# module.net
KiCad netlist of a schematic drawn in EAGLE
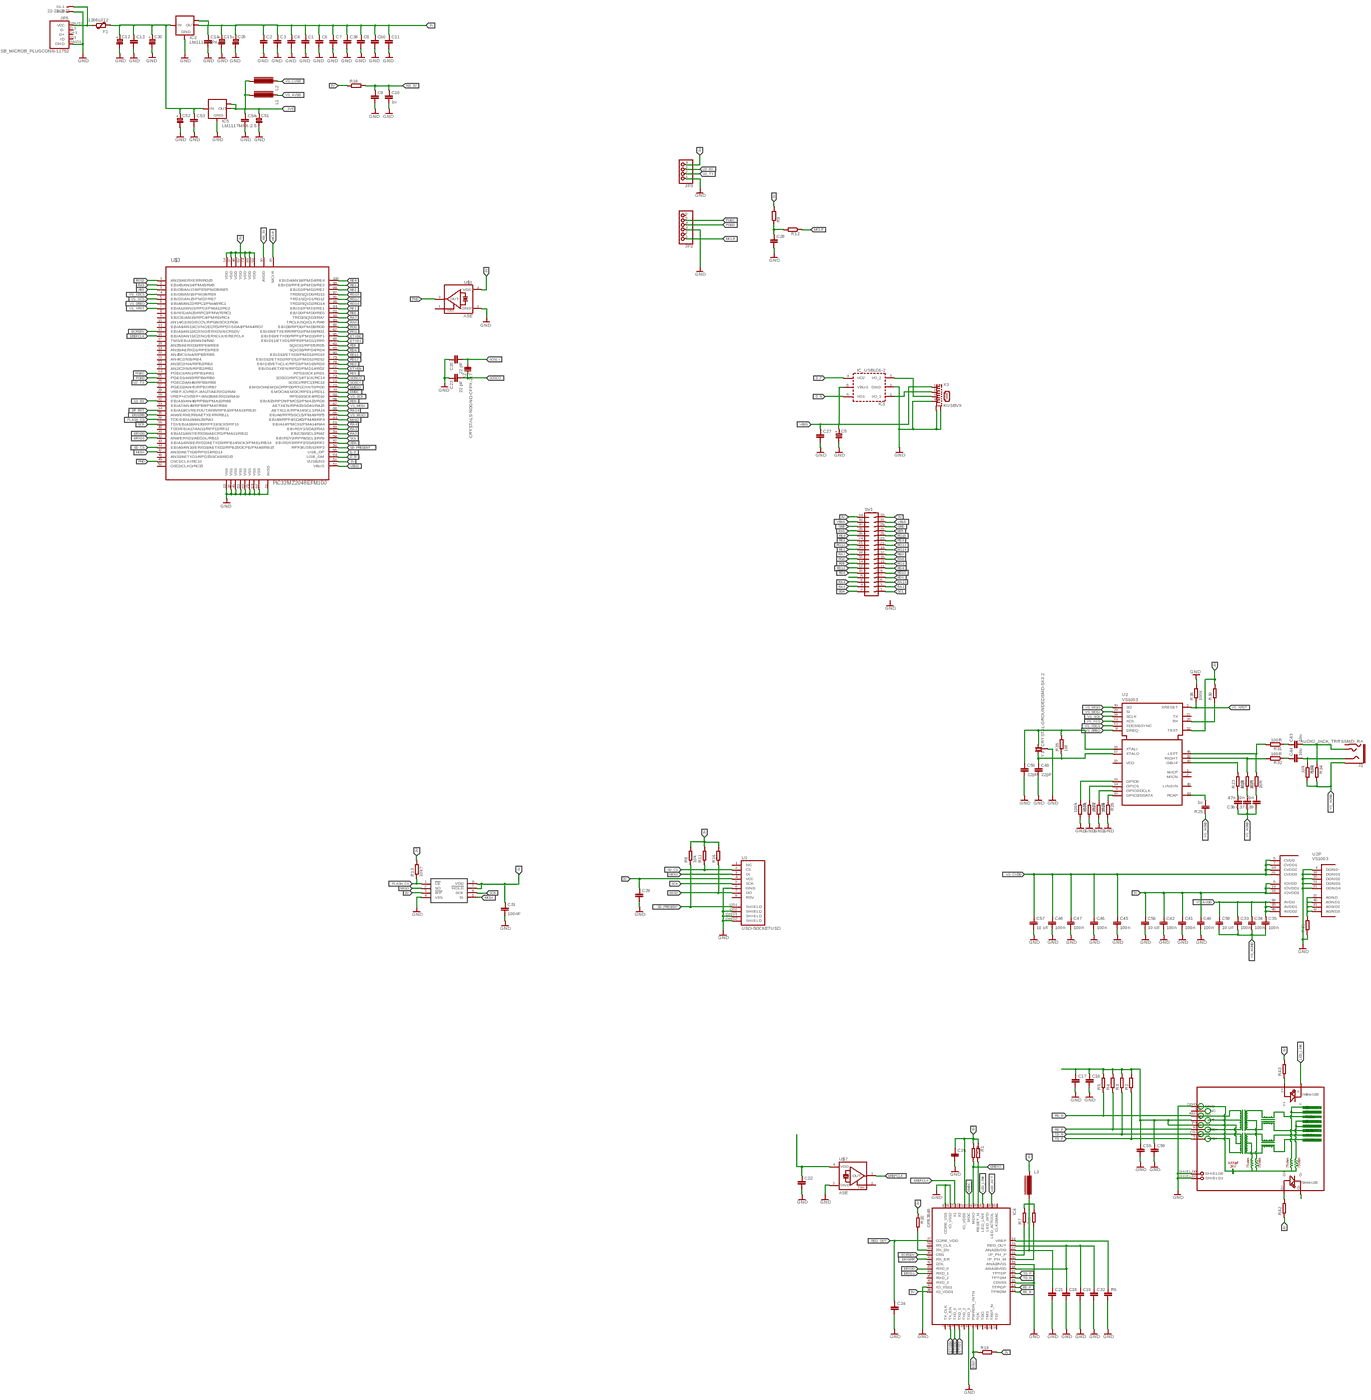
[diagram p0: schematic, sheet 1, overview]
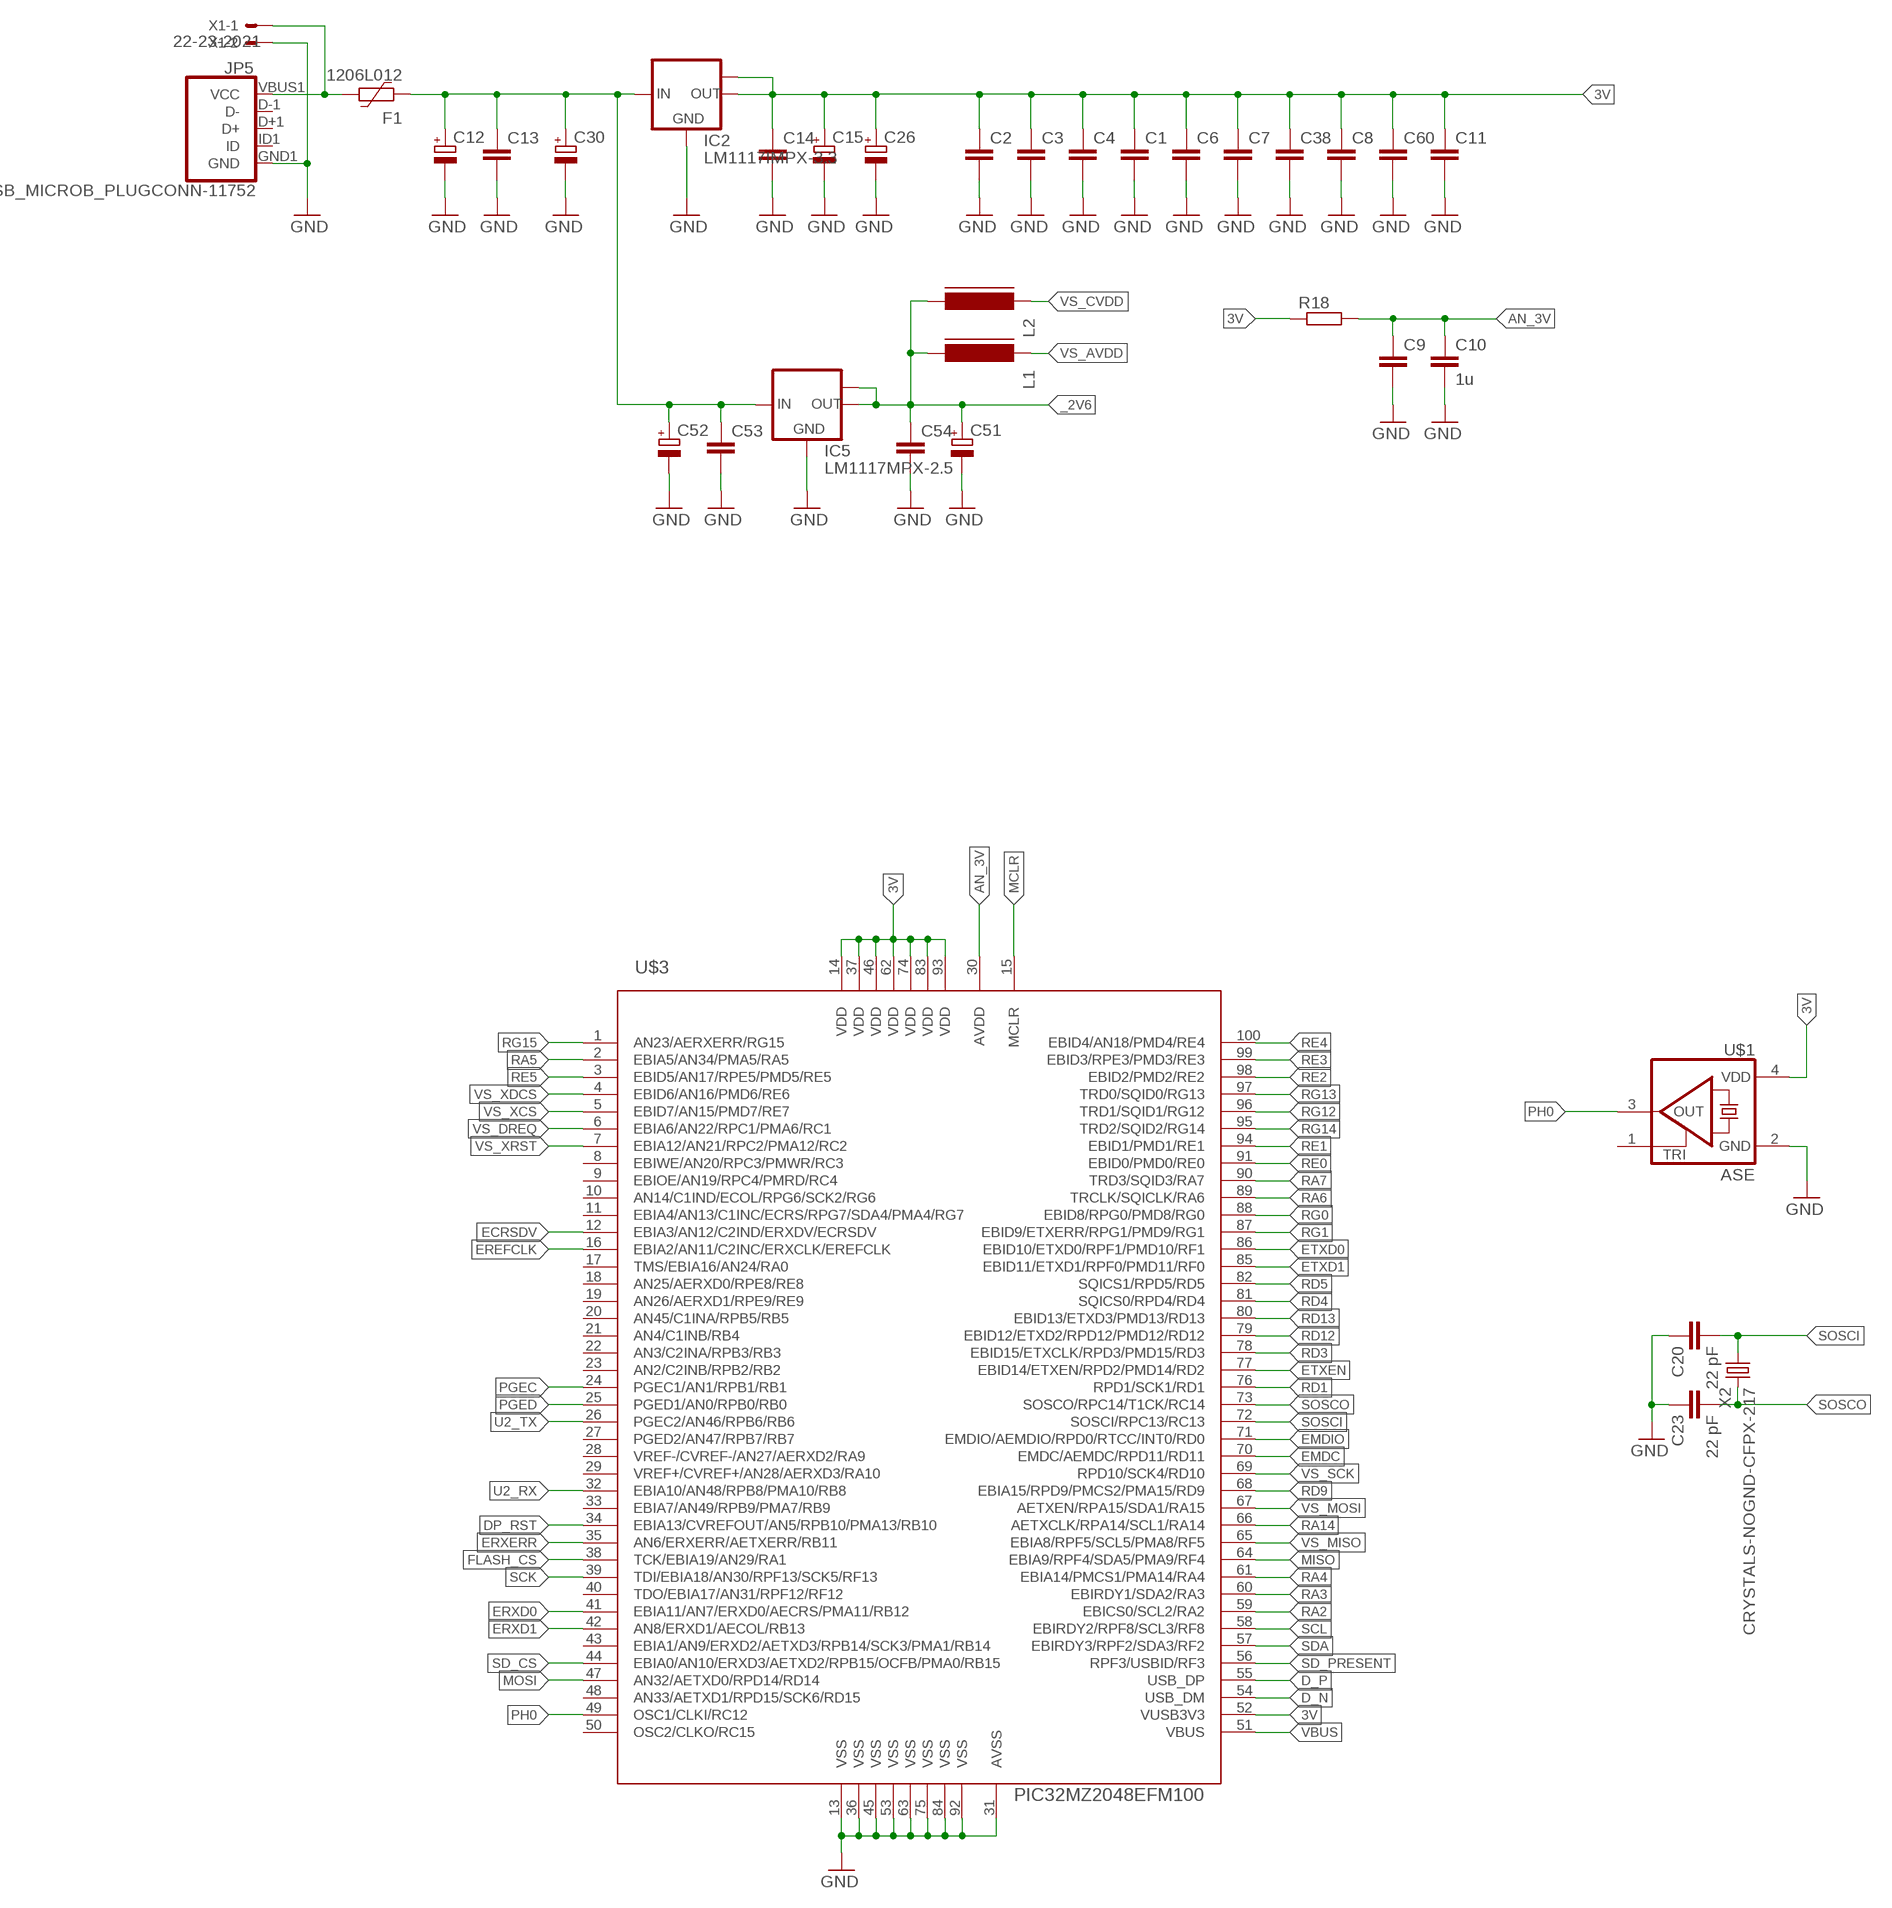
[diagram p1: schematic, sheet 1, part 1 of 4]
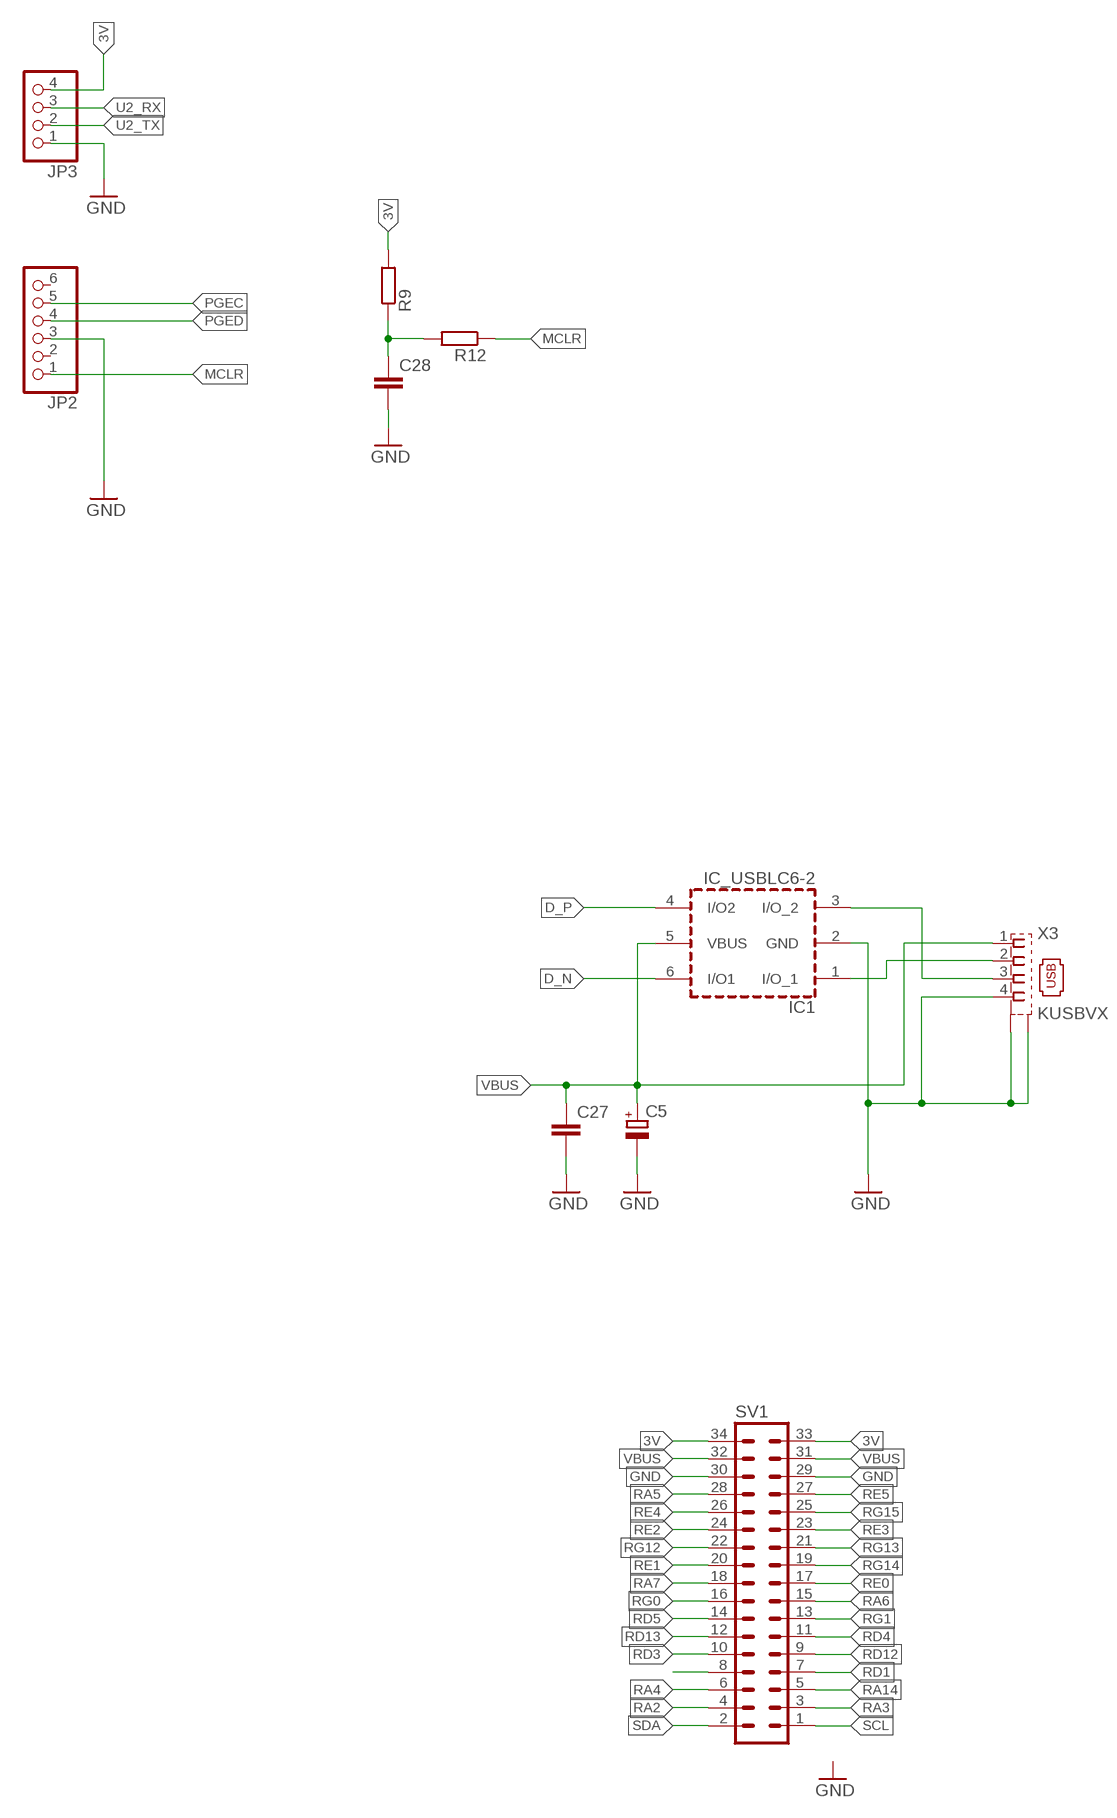
[diagram p2: schematic, sheet 1, part 2 of 4]
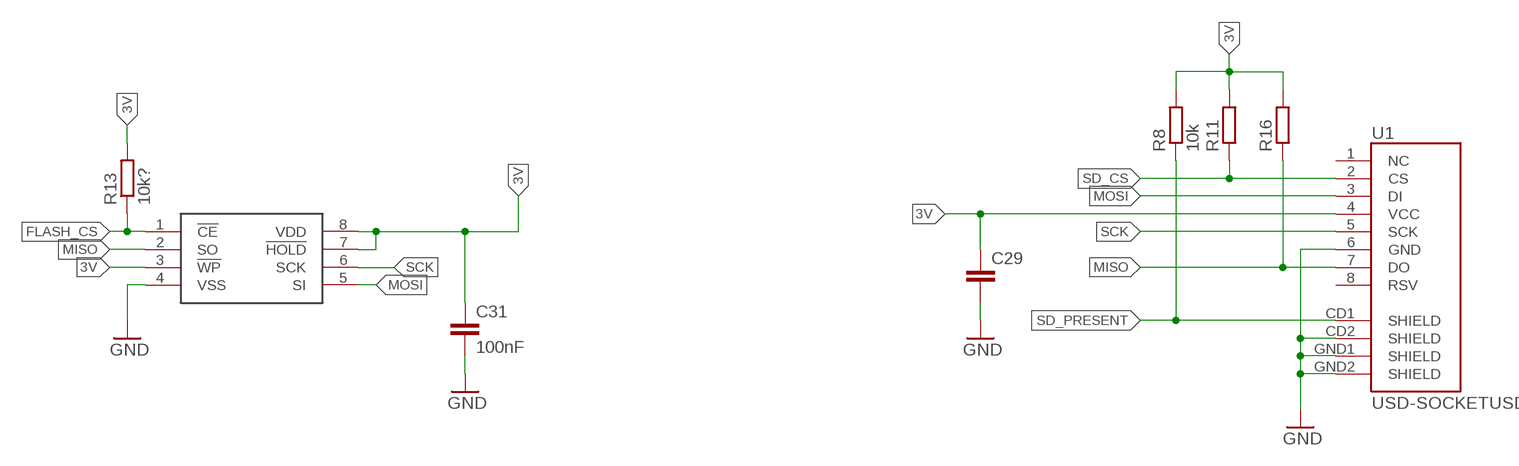
[diagram p3: schematic, sheet 1, part 3 of 4]
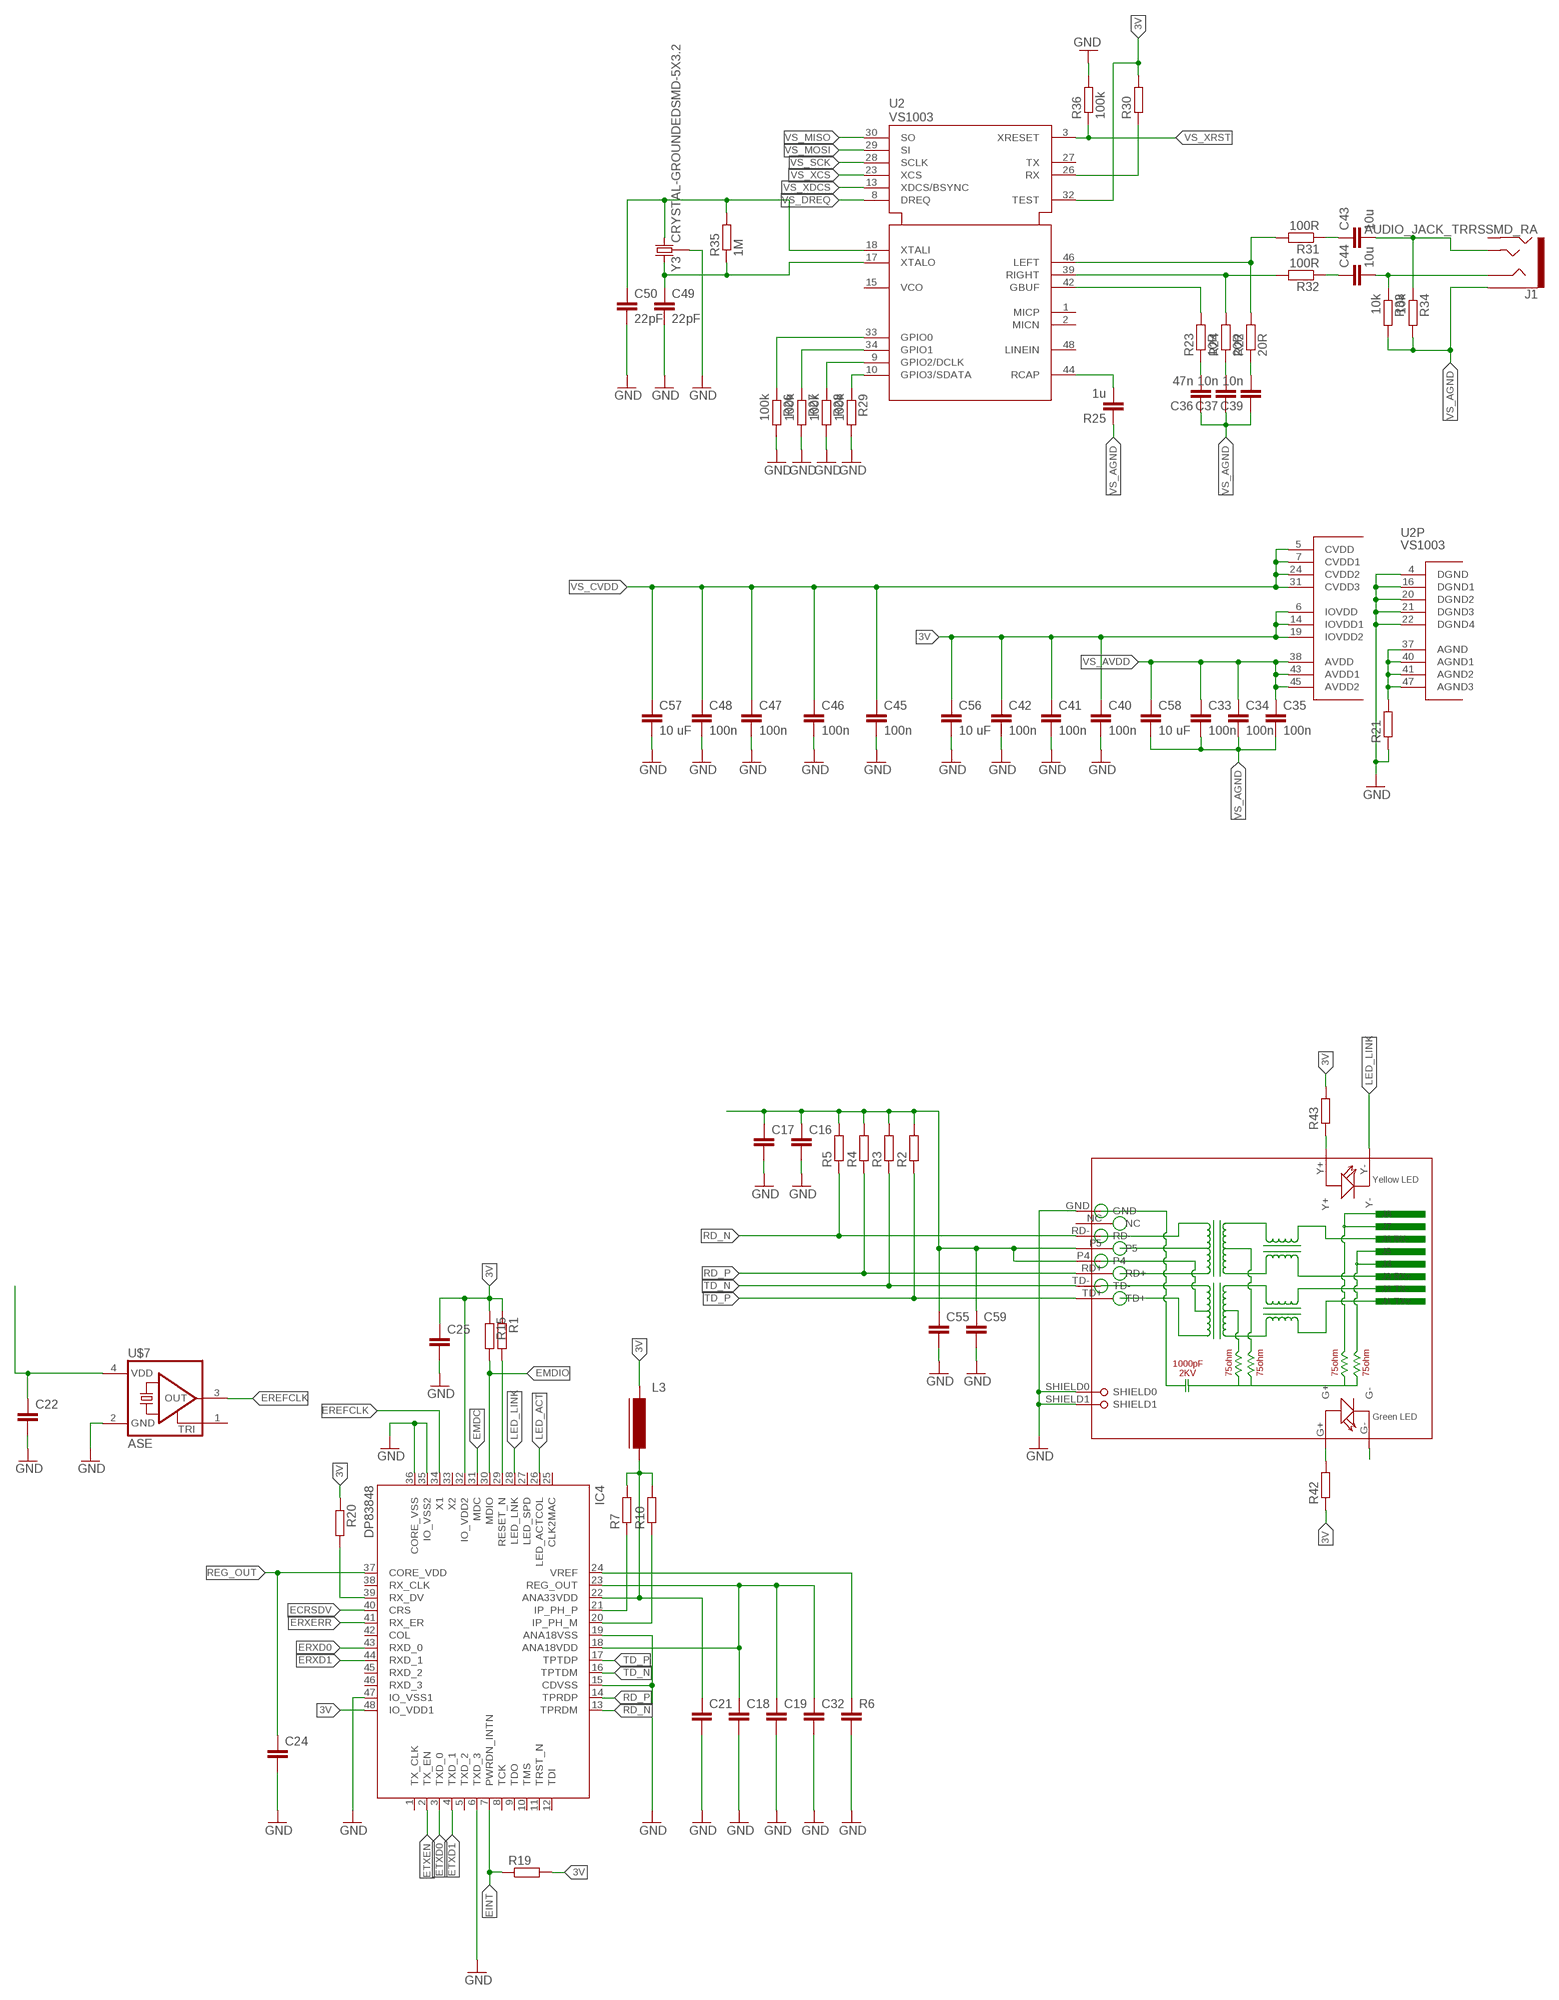
[diagram p4: schematic, sheet 1, part 4 of 4]

(export (version "E")
  (design (tool "Eeschema 10.0.6"))
  (components
    (comp (ref "C1")
      (value "C-EUC0402")
      (footprint "eagle-import:C0402")
      (libsource (lib "eagle-import") (part "C-EUC0402"))
    )
    (comp (ref "C2")
      (value "C-EUC0402")
      (footprint "eagle-import:C0402")
      (libsource (lib "eagle-import") (part "C-EUC0402"))
    )
    (comp (ref "C3")
      (value "C-EUC0402")
      (footprint "eagle-import:C0402")
      (libsource (lib "eagle-import") (part "C-EUC0402"))
    )
    (comp (ref "C4")
      (value "C-EUC0402")
      (footprint "eagle-import:C0402")
      (libsource (lib "eagle-import") (part "C-EUC0402"))
    )
    (comp (ref "C5")
      (value "CPOL-EUSMCA")
      (footprint "eagle-import:SMC_A")
      (libsource (lib "eagle-import") (part "CPOL-EUSMCA"))
    )
    (comp (ref "C6")
      (value "C-EUC0402")
      (footprint "eagle-import:C0402")
      (libsource (lib "eagle-import") (part "C-EUC0402"))
    )
    (comp (ref "C7")
      (value "C-EUC0402")
      (footprint "eagle-import:C0402")
      (libsource (lib "eagle-import") (part "C-EUC0402"))
    )
    (comp (ref "C8")
      (value "C-EUC0402")
      (footprint "eagle-import:C0402")
      (libsource (lib "eagle-import") (part "C-EUC0402"))
    )
    (comp (ref "C9")
      (value "C-EUC0402")
      (footprint "eagle-import:C0402")
      (libsource (lib "eagle-import") (part "C-EUC0402"))
    )
    (comp (ref "C10")
      (value "1u")
      (footprint "eagle-import:C0603")
      (libsource (lib "eagle-import") (part "C-EUC0603"))
    )
    (comp (ref "C11")
      (value "C-EUC0402")
      (footprint "eagle-import:C0402")
      (libsource (lib "eagle-import") (part "C-EUC0402"))
    )
    (comp (ref "C12")
      (value "CPOL-EUSMCB")
      (footprint "eagle-import:SMC_B")
      (libsource (lib "eagle-import") (part "CPOL-EUSMCB"))
    )
    (comp (ref "C13")
      (value "C-EUC0603")
      (footprint "eagle-import:C0603")
      (libsource (lib "eagle-import") (part "C-EUC0603"))
    )
    (comp (ref "C14")
      (value "C-EUC0603")
      (footprint "eagle-import:C0603")
      (libsource (lib "eagle-import") (part "C-EUC0603"))
    )
    (comp (ref "C15")
      (value "CPOL-EUSMCB")
      (footprint "eagle-import:SMC_B")
      (libsource (lib "eagle-import") (part "CPOL-EUSMCB"))
    )
    (comp (ref "C16")
      (value "C-EUC0603")
      (footprint "eagle-import:C0603")
      (libsource (lib "eagle-import") (part "C-EUC0603"))
    )
    (comp (ref "C17")
      (value "C-EUC0603")
      (footprint "eagle-import:C0603")
      (libsource (lib "eagle-import") (part "C-EUC0603"))
    )
    (comp (ref "C18")
      (value "C-EUC0402")
      (footprint "eagle-import:C0402")
      (libsource (lib "eagle-import") (part "C-EUC0402"))
    )
    (comp (ref "C19")
      (value "C-EUC0402")
      (footprint "eagle-import:C0402")
      (libsource (lib "eagle-import") (part "C-EUC0402"))
    )
    (comp (ref "C20")
      (value "22 pF")
      (footprint "eagle-import:C0603")
      (libsource (lib "eagle-import") (part "C-EUC0603"))
    )
    (comp (ref "C21")
      (value "C-EUC0402")
      (footprint "eagle-import:C0402")
      (libsource (lib "eagle-import") (part "C-EUC0402"))
    )
    (comp (ref "C22")
      (value "C-EUC0402")
      (footprint "eagle-import:C0402")
      (libsource (lib "eagle-import") (part "C-EUC0402"))
    )
    (comp (ref "C23")
      (value "22 pF")
      (footprint "eagle-import:C0603")
      (libsource (lib "eagle-import") (part "C-EUC0603"))
    )
    (comp (ref "C24")
      (value "C-EUC0603")
      (footprint "eagle-import:C0603")
      (libsource (lib "eagle-import") (part "C-EUC0603"))
    )
    (comp (ref "C25")
      (value "C-EUC0603")
      (footprint "eagle-import:C0603")
      (libsource (lib "eagle-import") (part "C-EUC0603"))
    )
    (comp (ref "C26")
      (value "CPOL-EUSMCA")
      (footprint "eagle-import:SMC_A")
      (libsource (lib "eagle-import") (part "CPOL-EUSMCA"))
    )
    (comp (ref "C27")
      (value "C-EUC0603")
      (footprint "eagle-import:C0603")
      (libsource (lib "eagle-import") (part "C-EUC0603"))
    )
    (comp (ref "C28")
      (value "C-EUC0603")
      (footprint "eagle-import:C0603")
      (libsource (lib "eagle-import") (part "C-EUC0603"))
    )
    (comp (ref "C29")
      (value "C-EUC0603")
      (footprint "eagle-import:C0603")
      (libsource (lib "eagle-import") (part "C-EUC0603"))
    )
    (comp (ref "C30")
      (value "CPOL-EUSMCA")
      (footprint "eagle-import:SMC_A")
      (libsource (lib "eagle-import") (part "CPOL-EUSMCA"))
    )
    (comp (ref "C31")
      (value "100nF")
      (footprint "eagle-import:C0603")
      (libsource (lib "eagle-import") (part "C-EUC0603"))
    )
    (comp (ref "C32")
      (value "C-EUC0603")
      (footprint "eagle-import:C0603")
      (libsource (lib "eagle-import") (part "C-EUC0603"))
    )
    (comp (ref "C33")
      (value "100n")
      (footprint "eagle-import:C0603")
      (libsource (lib "eagle-import") (part "C-EUC0603"))
    )
    (comp (ref "C34")
      (value "100n")
      (footprint "eagle-import:C0603")
      (libsource (lib "eagle-import") (part "C-EUC0603"))
    )
    (comp (ref "C35")
      (value "100n")
      (footprint "eagle-import:C0603")
      (libsource (lib "eagle-import") (part "C-EUC0603"))
    )
    (comp (ref "C36")
      (value "47n")
      (footprint "eagle-import:C0603")
      (libsource (lib "eagle-import") (part "C-EUC0603"))
    )
    (comp (ref "C37")
      (value "10n")
      (footprint "eagle-import:C0603")
      (libsource (lib "eagle-import") (part "C-EUC0603"))
    )
    (comp (ref "C38")
      (value "C-EUC0402")
      (footprint "eagle-import:C0402")
      (libsource (lib "eagle-import") (part "C-EUC0402"))
    )
    (comp (ref "C39")
      (value "10n")
      (footprint "eagle-import:C0603")
      (libsource (lib "eagle-import") (part "C-EUC0603"))
    )
    (comp (ref "C40")
      (value "100n")
      (footprint "eagle-import:C0402")
      (libsource (lib "eagle-import") (part "C-EUC0402"))
    )
    (comp (ref "C41")
      (value "100n")
      (footprint "eagle-import:C0402")
      (libsource (lib "eagle-import") (part "C-EUC0402"))
    )
    (comp (ref "C42")
      (value "100n")
      (footprint "eagle-import:C0402")
      (libsource (lib "eagle-import") (part "C-EUC0402"))
    )
    (comp (ref "C43")
      (value "10u")
      (footprint "eagle-import:C0603")
      (libsource (lib "eagle-import") (part "C-EUC0603"))
    )
    (comp (ref "C44")
      (value "10u")
      (footprint "eagle-import:C0603")
      (libsource (lib "eagle-import") (part "C-EUC0603"))
    )
    (comp (ref "C45")
      (value "100n")
      (footprint "eagle-import:C0402")
      (libsource (lib "eagle-import") (part "C-EUC0402"))
    )
    (comp (ref "C46")
      (value "100n")
      (footprint "eagle-import:C0603")
      (libsource (lib "eagle-import") (part "C-EUC0603"))
    )
    (comp (ref "C47")
      (value "100n")
      (footprint "eagle-import:C0603")
      (libsource (lib "eagle-import") (part "C-EUC0603"))
    )
    (comp (ref "C48")
      (value "100n")
      (footprint "eagle-import:C0603")
      (libsource (lib "eagle-import") (part "C-EUC0603"))
    )
    (comp (ref "C49")
      (value "22pF")
      (footprint "eagle-import:C0603")
      (libsource (lib "eagle-import") (part "C-EUC0603"))
    )
    (comp (ref "C50")
      (value "22pF")
      (footprint "eagle-import:C0603")
      (libsource (lib "eagle-import") (part "C-EUC0603"))
    )
    (comp (ref "C51")
      (value "CPOL-EUSMCB")
      (footprint "eagle-import:SMC_B")
      (libsource (lib "eagle-import") (part "CPOL-EUSMCB"))
    )
    (comp (ref "C52")
      (value "CPOL-EUSMCB")
      (footprint "eagle-import:SMC_B")
      (libsource (lib "eagle-import") (part "CPOL-EUSMCB"))
    )
    (comp (ref "C53")
      (value "C-EUC1206")
      (footprint "eagle-import:C1206")
      (libsource (lib "eagle-import") (part "C-EUC1206"))
    )
    (comp (ref "C54")
      (value "C-EUC1206")
      (footprint "eagle-import:C1206")
      (libsource (lib "eagle-import") (part "C-EUC1206"))
    )
    (comp (ref "C55")
      (value "C-EUC0603")
      (footprint "eagle-import:C0603")
      (libsource (lib "eagle-import") (part "C-EUC0603"))
    )
    (comp (ref "C56")
      (value "10 uF")
      (footprint "eagle-import:C0603")
      (libsource (lib "eagle-import") (part "C-EUC0603"))
    )
    (comp (ref "C57")
      (value "10 uF")
      (footprint "eagle-import:C0603")
      (libsource (lib "eagle-import") (part "C-EUC0603"))
    )
    (comp (ref "C58")
      (value "10 uF")
      (footprint "eagle-import:C0603")
      (libsource (lib "eagle-import") (part "C-EUC0603"))
    )
    (comp (ref "C59")
      (value "C-EUC0603")
      (footprint "eagle-import:C0603")
      (libsource (lib "eagle-import") (part "C-EUC0603"))
    )
    (comp (ref "C60")
      (value "C-EUC0402")
      (footprint "eagle-import:C0402")
      (libsource (lib "eagle-import") (part "C-EUC0402"))
    )
    (comp (ref "F1")
      (value "1206L012")
      (footprint "eagle-import:1206L")
      (fields (field (name "MF") "Littelfuse"))
      (libsource (lib "eagle-import") (part "?1206L012"))
    )
    (comp (ref "IC1")
      (value "IC_USBLC6-2")
      (footprint "eagle-import:SOT-23-6L")
      (libsource (lib "eagle-import") (part "IC_USBLC6-2"))
    )
    (comp (ref "IC2")
      (value "LM1117IMPX-3.3")
      (footprint "eagle-import:SOT223")
      (libsource (lib "eagle-import") (part "LM1117IMPX-3.3"))
    )
    (comp (ref "IC4")
      (value "DP83848")
      (footprint "eagle-import:LQFP48")
      (fields (field (name "MPN") "DP83848VYB"))
      (libsource (lib "eagle-import") (part "DP83848"))
    )
    (comp (ref "IC5")
      (value "LM1117MPX-2.5")
      (footprint "eagle-import:SOT223")
      (libsource (lib "eagle-import") (part "LM1117MPX-2.5"))
    )
    (comp (ref "J1")
      (value "AUDIO_JACK_TRRSSMD_RA")
      (footprint "eagle-import:AUDIO_JACK_3.5MM_TRRS_SMD_RA")
      (libsource (lib "eagle-import") (part "AUDIO_JACK_TRRSSMD_RA"))
    )
    (comp (ref "JP2")
      (value "PINHD-1X6")
      (footprint "eagle-import:1X06")
      (libsource (lib "eagle-import") (part "PINHD-1X6"))
    )
    (comp (ref "JP3")
      (value "PINHD-1X4")
      (footprint "eagle-import:1X04")
      (libsource (lib "eagle-import") (part "PINHD-1X4"))
    )
    (comp (ref "JP5")
      (value "USB_MICROB_PLUGCONN-11752")
      (footprint "eagle-import:USB-B-MICRO-SMD_V03")
      (libsource (lib "eagle-import") (part "USB_MICROB_PLUGCONN-11752"))
    )
    (comp (ref "L1")
      (value "FERRITE-0805")
      (footprint "eagle-import:FB805")
      (libsource (lib "eagle-import") (part "FERRITE-0805"))
    )
    (comp (ref "L2")
      (value "FERRITE-0805")
      (footprint "eagle-import:FB805")
      (libsource (lib "eagle-import") (part "FERRITE-0805"))
    )
    (comp (ref "L3")
      (value "FERRITE-0805")
      (footprint "eagle-import:FB805")
      (libsource (lib "eagle-import") (part "FERRITE-0805"))
    )
    (comp (ref "R1")
      (value "R-EU_R0402")
      (footprint "eagle-import:R0402")
      (libsource (lib "eagle-import") (part "R-EU_R0402"))
    )
    (comp (ref "R2")
      (value "R-EU_R0603")
      (footprint "eagle-import:R0603")
      (libsource (lib "eagle-import") (part "R-EU_R0603"))
    )
    (comp (ref "R3")
      (value "R-EU_R0603")
      (footprint "eagle-import:R0603")
      (libsource (lib "eagle-import") (part "R-EU_R0603"))
    )
    (comp (ref "R4")
      (value "R-EU_R0603")
      (footprint "eagle-import:R0603")
      (libsource (lib "eagle-import") (part "R-EU_R0603"))
    )
    (comp (ref "R5")
      (value "R-EU_R0603")
      (footprint "eagle-import:R0603")
      (libsource (lib "eagle-import") (part "R-EU_R0603"))
    )
    (comp (ref "R6")
      (value "C-EUC0603")
      (footprint "eagle-import:C0603")
      (libsource (lib "eagle-import") (part "C-EUC0603"))
    )
    (comp (ref "R7")
      (value "R-EU_R0402")
      (footprint "eagle-import:R0402")
      (libsource (lib "eagle-import") (part "R-EU_R0402"))
    )
    (comp (ref "R8")
      (value "10k")
      (footprint "eagle-import:R0603")
      (libsource (lib "eagle-import") (part "R-EU_R0603"))
    )
    (comp (ref "R9")
      (value "R-EU_R0603")
      (footprint "eagle-import:R0603")
      (libsource (lib "eagle-import") (part "R-EU_R0603"))
    )
    (comp (ref "R10")
      (value "R-EU_R0402")
      (footprint "eagle-import:R0402")
      (libsource (lib "eagle-import") (part "R-EU_R0402"))
    )
    (comp (ref "R11")
      (value "R-EU_R0603")
      (footprint "eagle-import:R0603")
      (libsource (lib "eagle-import") (part "R-EU_R0603"))
    )
    (comp (ref "R12")
      (value "R-EU_R0402")
      (footprint "eagle-import:R0402")
      (libsource (lib "eagle-import") (part "R-EU_R0402"))
    )
    (comp (ref "R13")
      (value "10k?")
      (footprint "eagle-import:R0603")
      (libsource (lib "eagle-import") (part "R-EU_R0603"))
    )
    (comp (ref "R15")
      (value "R-EU_R0603")
      (footprint "eagle-import:R0603")
      (libsource (lib "eagle-import") (part "R-EU_R0603"))
    )
    (comp (ref "R16")
      (value "R-EU_R0603")
      (footprint "eagle-import:R0603")
      (libsource (lib "eagle-import") (part "R-EU_R0603"))
    )
    (comp (ref "R18")
      (value "R-EU_R0805")
      (footprint "eagle-import:R0805")
      (libsource (lib "eagle-import") (part "R-EU_R0805"))
    )
    (comp (ref "R19")
      (value "R-EU_R0402")
      (footprint "eagle-import:R0402")
      (libsource (lib "eagle-import") (part "R-EU_R0402"))
    )
    (comp (ref "R20")
      (value "R-EU_R0603")
      (footprint "eagle-import:R0603")
      (libsource (lib "eagle-import") (part "R-EU_R0603"))
    )
    (comp (ref "R21")
      (value "R-EU_R0603")
      (footprint "eagle-import:R0603")
      (libsource (lib "eagle-import") (part "R-EU_R0603"))
    )
    (comp (ref "R22")
      (value "20R")
      (footprint "eagle-import:R0603")
      (libsource (lib "eagle-import") (part "R-EU_R0603"))
    )
    (comp (ref "R23")
      (value "10R")
      (footprint "eagle-import:R0603")
      (libsource (lib "eagle-import") (part "R-EU_R0603"))
    )
    (comp (ref "R24")
      (value "20R")
      (footprint "eagle-import:R0603")
      (libsource (lib "eagle-import") (part "R-EU_R0603"))
    )
    (comp (ref "R25")
      (value "1u")
      (footprint "eagle-import:C0603")
      (libsource (lib "eagle-import") (part "C-EUC0603"))
    )
    (comp (ref "R26")
      (value "100k")
      (footprint "eagle-import:R0402")
      (libsource (lib "eagle-import") (part "R-EU_R0402"))
    )
    (comp (ref "R27")
      (value "100k")
      (footprint "eagle-import:R0402")
      (libsource (lib "eagle-import") (part "R-EU_R0402"))
    )
    (comp (ref "R28")
      (value "100k")
      (footprint "eagle-import:R0402")
      (libsource (lib "eagle-import") (part "R-EU_R0402"))
    )
    (comp (ref "R29")
      (value "100k")
      (footprint "eagle-import:R0402")
      (libsource (lib "eagle-import") (part "R-EU_R0402"))
    )
    (comp (ref "R30")
      (value "R-EU_0204/7")
      (footprint "eagle-import:0204_7")
      (libsource (lib "eagle-import") (part "R-EU_0204/7"))
    )
    (comp (ref "R31")
      (value "100R")
      (footprint "eagle-import:R0603")
      (libsource (lib "eagle-import") (part "R-EU_R0603"))
    )
    (comp (ref "R32")
      (value "100R")
      (footprint "eagle-import:R0603")
      (libsource (lib "eagle-import") (part "R-EU_R0603"))
    )
    (comp (ref "R33")
      (value "10k")
      (footprint "eagle-import:R0603")
      (libsource (lib "eagle-import") (part "R-EU_R0603"))
    )
    (comp (ref "R34")
      (value "10k")
      (footprint "eagle-import:R0603")
      (libsource (lib "eagle-import") (part "R-EU_R0603"))
    )
    (comp (ref "R35")
      (value "1M")
      (footprint "eagle-import:R0603")
      (libsource (lib "eagle-import") (part "R-EU_R0603"))
    )
    (comp (ref "R36")
      (value "100k")
      (footprint "eagle-import:R0603")
      (libsource (lib "eagle-import") (part "R-EU_R0603"))
    )
    (comp (ref "R42")
      (value "R-EU_R0603")
      (footprint "eagle-import:R0603")
      (libsource (lib "eagle-import") (part "R-EU_R0603"))
    )
    (comp (ref "R43")
      (value "R-EU_R0603")
      (footprint "eagle-import:R0603")
      (libsource (lib "eagle-import") (part "R-EU_R0603"))
    )
    (comp (ref "RJ1")
      (value "HR911105A")
      (footprint "eagle-import:HR911105A")
      (libsource (lib "eagle-import") (part "HR911105A"))
    )
    (comp (ref "SV1")
      (value "ML34L")
      (footprint "eagle-import:ML34L")
      (libsource (lib "eagle-import") (part "ML34L"))
    )
    (comp (ref "U$1")
      (value "ASE")
      (footprint "eagle-import:ASE")
      (libsource (lib "eagle-import") (part "ASE"))
    )
    (comp (ref "U$2")
      (value "SST25VF016BSO8M")
      (footprint "eagle-import:SO-08M")
      (libsource (lib "eagle-import") (part "SST25VF016BSO8M"))
    )
    (comp (ref "U$3")
      (value "PIC32MZ2048EFM100")
      (footprint "eagle-import:TQFP100_12X12")
      (libsource (lib "eagle-import") (part "PIC32MZ2048EFM100"))
    )
    (comp (ref "U$7")
      (value "ASE")
      (footprint "eagle-import:ASE")
      (libsource (lib "eagle-import") (part "ASE"))
    )
    (comp (ref "U1")
      (value "USD-SOCKETUSD")
      (footprint "eagle-import:USD-SOCKET-PP")
      (libsource (lib "eagle-import") (part "USD-SOCKETUSD"))
    )
    (comp (ref "U2")
      (value "VS1003")
      (footprint "eagle-import:LQFP48")
      (libsource (lib "eagle-import") (part "VS1003"))
    )
    (comp (ref "X1")
      (value "22-23-2021")
      (footprint "eagle-import:22-23-2021")
      (fields (field (name "MF") "MOLEX"))
      (libsource (lib "eagle-import") (part "22-23-2021"))
    )
    (comp (ref "X2")
      (value "CRYSTALS-NOGND-CFPX-217")
      (footprint "eagle-import:3.2X1.5-2-PAD")
      (libsource (lib "eagle-import") (part "CRYSTALS-NOGND-CFPX-217"))
    )
    (comp (ref "X3")
      (value "KUSBVX")
      (footprint "eagle-import:KUSBVX")
      (libsource (lib "eagle-import") (part "KUSBVX"))
    )
    (comp (ref "Y3")
      (value "CRYSTAL-GROUNDEDSMD-5X3.2")
      (footprint "eagle-import:CRYSTAL-SMD-5X3.2-4PAD")
      (libsource (lib "eagle-import") (part "CRYSTAL-GROUNDEDSMD-5X3.2"))
    )
  )
  (nets
    (net (code "1") (name "/A3V") (class "Default")
      (node (ref "C16") (pin "1") (pinfunction "1_1") (pintype "passive"))
      (node (ref "C17") (pin "1") (pinfunction "1_1") (pintype "passive"))
      (node (ref "C21") (pin "1") (pinfunction "1_1") (pintype "passive"))
      (node (ref "C55") (pin "1") (pinfunction "1_1") (pintype "passive"))
      (node (ref "C59") (pin "1") (pinfunction "1_1") (pintype "passive"))
      (node (ref "IC4") (pin "22") (pinfunction "ANA33VDD_22") (pintype "power_in"))
      (node (ref "L3") (pin "2") (pinfunction "2_2") (pintype "passive"))
      (node (ref "R10") (pin "2") (pinfunction "2_2") (pintype "passive"))
      (node (ref "R2") (pin "2") (pinfunction "2_2") (pintype "passive"))
      (node (ref "R3") (pin "2") (pinfunction "2_2") (pintype "passive"))
      (node (ref "R4") (pin "2") (pinfunction "2_2") (pintype "passive"))
      (node (ref "R5") (pin "2") (pinfunction "2_2") (pintype "passive"))
      (node (ref "R7") (pin "2") (pinfunction "2_2") (pintype "passive"))
      (node (ref "RJ1") (pin "P4") (pinfunction "P4_P4") (pintype "bidirectional"))
      (node (ref "RJ1") (pin "P5") (pinfunction "P5_P5") (pintype "bidirectional"))
    )
    (net (code "2") (name "3V") (class "Default")
      (node (ref "C1") (pin "1") (pinfunction "1_1") (pintype "passive"))
      (node (ref "C11") (pin "1") (pinfunction "1_1") (pintype "passive"))
      (node (ref "C14") (pin "1") (pinfunction "1_1") (pintype "passive"))
      (node (ref "C15") (pin "+") (pinfunction "+_+") (pintype "passive"))
      (node (ref "C2") (pin "1") (pinfunction "1_1") (pintype "passive"))
      (node (ref "C22") (pin "1") (pinfunction "1_1") (pintype "passive"))
      (node (ref "C25") (pin "1") (pinfunction "1_1") (pintype "passive"))
      (node (ref "C26") (pin "+") (pinfunction "+_+") (pintype "passive"))
      (node (ref "C29") (pin "1") (pinfunction "1_1") (pintype "passive"))
      (node (ref "C3") (pin "1") (pinfunction "1_1") (pintype "passive"))
      (node (ref "C31") (pin "1") (pinfunction "1_1") (pintype "passive"))
      (node (ref "C38") (pin "1") (pinfunction "1_1") (pintype "passive"))
      (node (ref "C4") (pin "1") (pinfunction "1_1") (pintype "passive"))
      (node (ref "C40") (pin "1") (pinfunction "1_1") (pintype "passive"))
      (node (ref "C41") (pin "1") (pinfunction "1_1") (pintype "passive"))
      (node (ref "C42") (pin "1") (pinfunction "1_1") (pintype "passive"))
      (node (ref "C56") (pin "1") (pinfunction "1_1") (pintype "passive"))
      (node (ref "C6") (pin "1") (pinfunction "1_1") (pintype "passive"))
      (node (ref "C60") (pin "1") (pinfunction "1_1") (pintype "passive"))
      (node (ref "C7") (pin "1") (pinfunction "1_1") (pintype "passive"))
      (node (ref "C8") (pin "1") (pinfunction "1_1") (pintype "passive"))
      (node (ref "IC2") (pin "2") (pinfunction "OUT_2") (pintype "passive"))
      (node (ref "IC2") (pin "TAB") (pinfunction "OUT1_TAB") (pintype "passive"))
      (node (ref "IC4") (pin "32") (pinfunction "IO_VDD2_32") (pintype "power_in"))
      (node (ref "IC4") (pin "48") (pinfunction "IO_VDD1_48") (pintype "power_in"))
      (node (ref "JP3") (pin "4") (pinfunction "4_4") (pintype "passive"))
      (node (ref "L3") (pin "1") (pinfunction "1_1") (pintype "passive"))
      (node (ref "R1") (pin "1") (pinfunction "1_1") (pintype "passive"))
      (node (ref "R11") (pin "2") (pinfunction "2_2") (pintype "passive"))
      (node (ref "R13") (pin "2") (pinfunction "2_2") (pintype "passive"))
      (node (ref "R15") (pin "1") (pinfunction "1_1") (pintype "passive"))
      (node (ref "R16") (pin "2") (pinfunction "2_2") (pintype "passive"))
      (node (ref "R18") (pin "1") (pinfunction "1_1") (pintype "passive"))
      (node (ref "R19") (pin "2") (pinfunction "2_2") (pintype "passive"))
      (node (ref "R20") (pin "1") (pinfunction "1_1") (pintype "passive"))
      (node (ref "R30") (pin "2") (pinfunction "2_2") (pintype "passive"))
      (node (ref "R42") (pin "1") (pinfunction "1_1") (pintype "passive"))
      (node (ref "R43") (pin "2") (pinfunction "2_2") (pintype "passive"))
      (node (ref "R8") (pin "2") (pinfunction "2_2") (pintype "passive"))
      (node (ref "R9") (pin "2") (pinfunction "2_2") (pintype "passive"))
      (node (ref "SV1") (pin "33") (pinfunction "33_33") (pintype "passive"))
      (node (ref "SV1") (pin "34") (pinfunction "34_34") (pintype "passive"))
      (node (ref "U$1") (pin "4") (pinfunction "VDD_4") (pintype "power_in"))
      (node (ref "U$2") (pin "3") (pinfunction "~{WP}_3") (pintype "bidirectional"))
      (node (ref "U$2") (pin "7") (pinfunction "~{HOLD}_7") (pintype "bidirectional"))
      (node (ref "U$2") (pin "8") (pinfunction "VDD_8") (pintype "bidirectional"))
      (node (ref "U$3") (pin "14") (pinfunction "VDD_14") (pintype "bidirectional"))
      (node (ref "U$3") (pin "37") (pinfunction "VDD_37") (pintype "bidirectional"))
      (node (ref "U$3") (pin "46") (pinfunction "VDD_46") (pintype "bidirectional"))
      (node (ref "U$3") (pin "52") (pinfunction "VUSB3V3_52") (pintype "bidirectional"))
      (node (ref "U$3") (pin "62") (pinfunction "VDD_62") (pintype "bidirectional"))
      (node (ref "U$3") (pin "74") (pinfunction "VDD_74") (pintype "bidirectional"))
      (node (ref "U$3") (pin "83") (pinfunction "VDD_83") (pintype "bidirectional"))
      (node (ref "U$3") (pin "93") (pinfunction "VDD_93") (pintype "bidirectional"))
      (node (ref "U$7") (pin "4") (pinfunction "VDD_4") (pintype "power_in"))
      (node (ref "U1") (pin "4") (pinfunction "VCC_4") (pintype "bidirectional"))
      (node (ref "U2") (pin "14") (pinfunction "IOVDD1_14") (pintype "power_in"))
      (node (ref "U2") (pin "19") (pinfunction "IOVDD2_19") (pintype "power_in"))
      (node (ref "U2") (pin "32") (pinfunction "TEST_32") (pintype "bidirectional"))
      (node (ref "U2") (pin "6") (pinfunction "IOVDD_6") (pintype "power_in"))
    )
    (net (code "3") (name "AN_3V") (class "Default")
      (node (ref "C10") (pin "1") (pinfunction "1_1") (pintype "passive"))
      (node (ref "C9") (pin "1") (pinfunction "1_1") (pintype "passive"))
      (node (ref "R18") (pin "2") (pinfunction "2_2") (pintype "passive"))
      (node (ref "U$3") (pin "30") (pinfunction "AVDD_30") (pintype "bidirectional"))
    )
    (net (code "4") (name "DP_RST") (class "Default")
      (node (ref "IC4") (pin "29") (pinfunction "RESET_N_29") (pintype "input"))
      (node (ref "R1") (pin "2") (pinfunction "2_2") (pintype "passive"))
      (node (ref "U$3") (pin "34") (pinfunction "EBIA13/CVREFOUT/AN5/RPB10/PMA13/RB10_34") (pintype "bidirectional"))
    )
    (net (code "5") (name "D_N") (class "Default")
      (node (ref "IC1") (pin "6") (pinfunction "I/O1_6") (pintype "bidirectional"))
      (node (ref "U$3") (pin "54") (pinfunction "USB_DM_54") (pintype "bidirectional"))
    )
    (net (code "6") (name "D_P") (class "Default")
      (node (ref "IC1") (pin "4") (pinfunction "I/O2_4") (pintype "bidirectional"))
      (node (ref "U$3") (pin "55") (pinfunction "USB_DP_55") (pintype "bidirectional"))
    )
    (net (code "7") (name "ECRSDV") (class "Default")
      (node (ref "IC4") (pin "40") (pinfunction "CRS_40") (pintype "bidirectional"))
      (node (ref "U$3") (pin "12") (pinfunction "EBIA3/AN12/C2IND/ERXDV/ECRSDV_12") (pintype "bidirectional"))
    )
    (net (code "8") (name "EINT") (class "Default")
      (node (ref "IC4") (pin "7") (pinfunction "PWRDN_INTN_7") (pintype "bidirectional"))
      (node (ref "R19") (pin "1") (pinfunction "1_1") (pintype "passive"))
    )
    (net (code "9") (name "EMDC") (class "Default")
      (node (ref "IC4") (pin "31") (pinfunction "MDC_31") (pintype "input"))
      (node (ref "U$3") (pin "70") (pinfunction "EMDC/AEMDC/RPD11/RD11_70") (pintype "bidirectional"))
    )
    (net (code "10") (name "EMDIO") (class "Default")
      (node (ref "IC4") (pin "30") (pinfunction "MDIO_30") (pintype "bidirectional"))
      (node (ref "R15") (pin "2") (pinfunction "2_2") (pintype "passive"))
      (node (ref "U$3") (pin "71") (pinfunction "EMDIO/AEMDIO/RPD0/RTCC/INT0/RD0_71") (pintype "bidirectional"))
    )
    (net (code "11") (name "EREFCLK") (class "Default")
      (node (ref "IC4") (pin "34") (pinfunction "X1_34") (pintype "input"))
      (node (ref "U$3") (pin "16") (pinfunction "EBIA2/AN11/C2INC/ERXCLK/EREFCLK_16") (pintype "bidirectional"))
      (node (ref "U$7") (pin "3") (pinfunction "OUT_3") (pintype "output"))
    )
    (net (code "12") (name "ERXD0") (class "Default")
      (node (ref "IC4") (pin "43") (pinfunction "RXD_0_43") (pintype "bidirectional"))
      (node (ref "U$3") (pin "41") (pinfunction "EBIA11/AN7/ERXD0/AECRS/PMA11/RB12_41") (pintype "bidirectional"))
    )
    (net (code "13") (name "ERXD1") (class "Default")
      (node (ref "IC4") (pin "44") (pinfunction "RXD_1_44") (pintype "bidirectional"))
      (node (ref "U$3") (pin "42") (pinfunction "AN8/ERXD1/AECOL/RB13_42") (pintype "bidirectional"))
    )
    (net (code "14") (name "ERXERR") (class "Default")
      (node (ref "IC4") (pin "41") (pinfunction "RX_ER_41") (pintype "bidirectional"))
      (node (ref "U$3") (pin "35") (pinfunction "AN6/ERXERR/AETXERR/RB11_35") (pintype "bidirectional"))
    )
    (net (code "15") (name "ETXD0") (class "Default")
      (node (ref "IC4") (pin "3") (pinfunction "TXD_0_3") (pintype "bidirectional"))
      (node (ref "U$3") (pin "86") (pinfunction "EBID10/ETXD0/RPF1/PMD10/RF1_86") (pintype "bidirectional"))
    )
    (net (code "16") (name "ETXD1") (class "Default")
      (node (ref "IC4") (pin "4") (pinfunction "TXD_1_4") (pintype "bidirectional"))
      (node (ref "U$3") (pin "85") (pinfunction "EBID11/ETXD1/RPF0/PMD11/RF0_85") (pintype "bidirectional"))
    )
    (net (code "17") (name "ETXEN") (class "Default")
      (node (ref "IC4") (pin "2") (pinfunction "TX_EN_2") (pintype "bidirectional"))
      (node (ref "U$3") (pin "77") (pinfunction "EBID14/ETXEN/RPD2/PMD14/RD2_77") (pintype "bidirectional"))
    )
    (net (code "18") (name "FLASH_CS") (class "Default")
      (node (ref "R13") (pin "1") (pinfunction "1_1") (pintype "passive"))
      (node (ref "U$2") (pin "1") (pinfunction "~{CE}_1") (pintype "bidirectional"))
      (node (ref "U$3") (pin "38") (pinfunction "TCK/EBIA19/AN29/RA1_38") (pintype "bidirectional"))
    )
    (net (code "19") (name "GND") (class "Default")
      (node (ref "C1") (pin "2") (pinfunction "2_2") (pintype "passive"))
      (node (ref "C10") (pin "2") (pinfunction "2_2") (pintype "passive"))
      (node (ref "C11") (pin "2") (pinfunction "2_2") (pintype "passive"))
      (node (ref "C12") (pin "-") (pinfunction "-_-") (pintype "passive"))
      (node (ref "C13") (pin "2") (pinfunction "2_2") (pintype "passive"))
      (node (ref "C14") (pin "2") (pinfunction "2_2") (pintype "passive"))
      (node (ref "C15") (pin "-") (pinfunction "-_-") (pintype "passive"))
      (node (ref "C16") (pin "2") (pinfunction "2_2") (pintype "passive"))
      (node (ref "C17") (pin "2") (pinfunction "2_2") (pintype "passive"))
      (node (ref "C18") (pin "2") (pinfunction "2_2") (pintype "passive"))
      (node (ref "C19") (pin "2") (pinfunction "2_2") (pintype "passive"))
      (node (ref "C2") (pin "2") (pinfunction "2_2") (pintype "passive"))
      (node (ref "C20") (pin "1") (pinfunction "1_1") (pintype "passive"))
      (node (ref "C21") (pin "2") (pinfunction "2_2") (pintype "passive"))
      (node (ref "C22") (pin "2") (pinfunction "2_2") (pintype "passive"))
      (node (ref "C23") (pin "1") (pinfunction "1_1") (pintype "passive"))
      (node (ref "C24") (pin "2") (pinfunction "2_2") (pintype "passive"))
      (node (ref "C25") (pin "2") (pinfunction "2_2") (pintype "passive"))
      (node (ref "C26") (pin "-") (pinfunction "-_-") (pintype "passive"))
      (node (ref "C27") (pin "2") (pinfunction "2_2") (pintype "passive"))
      (node (ref "C28") (pin "2") (pinfunction "2_2") (pintype "passive"))
      (node (ref "C29") (pin "2") (pinfunction "2_2") (pintype "passive"))
      (node (ref "C3") (pin "2") (pinfunction "2_2") (pintype "passive"))
      (node (ref "C30") (pin "-") (pinfunction "-_-") (pintype "passive"))
      (node (ref "C31") (pin "2") (pinfunction "2_2") (pintype "passive"))
      (node (ref "C32") (pin "2") (pinfunction "2_2") (pintype "passive"))
      (node (ref "C38") (pin "2") (pinfunction "2_2") (pintype "passive"))
      (node (ref "C4") (pin "2") (pinfunction "2_2") (pintype "passive"))
      (node (ref "C40") (pin "2") (pinfunction "2_2") (pintype "passive"))
      (node (ref "C41") (pin "2") (pinfunction "2_2") (pintype "passive"))
      (node (ref "C42") (pin "2") (pinfunction "2_2") (pintype "passive"))
      (node (ref "C45") (pin "2") (pinfunction "2_2") (pintype "passive"))
      (node (ref "C46") (pin "2") (pinfunction "2_2") (pintype "passive"))
      (node (ref "C47") (pin "2") (pinfunction "2_2") (pintype "passive"))
      (node (ref "C48") (pin "2") (pinfunction "2_2") (pintype "passive"))
      (node (ref "C49") (pin "2") (pinfunction "2_2") (pintype "passive"))
      (node (ref "C5") (pin "-") (pinfunction "-_-") (pintype "passive"))
      (node (ref "C50") (pin "2") (pinfunction "2_2") (pintype "passive"))
      (node (ref "C51") (pin "-") (pinfunction "-_-") (pintype "passive"))
      (node (ref "C52") (pin "-") (pinfunction "-_-") (pintype "passive"))
      (node (ref "C53") (pin "2") (pinfunction "2_2") (pintype "passive"))
      (node (ref "C54") (pin "2") (pinfunction "2_2") (pintype "passive"))
      (node (ref "C55") (pin "2") (pinfunction "2_2") (pintype "passive"))
      (node (ref "C56") (pin "2") (pinfunction "2_2") (pintype "passive"))
      (node (ref "C57") (pin "2") (pinfunction "2_2") (pintype "passive"))
      (node (ref "C59") (pin "2") (pinfunction "2_2") (pintype "passive"))
      (node (ref "C6") (pin "2") (pinfunction "2_2") (pintype "passive"))
      (node (ref "C60") (pin "2") (pinfunction "2_2") (pintype "passive"))
      (node (ref "C7") (pin "2") (pinfunction "2_2") (pintype "passive"))
      (node (ref "C8") (pin "2") (pinfunction "2_2") (pintype "passive"))
      (node (ref "C9") (pin "2") (pinfunction "2_2") (pintype "passive"))
      (node (ref "IC1") (pin "2") (pinfunction "GND_2") (pintype "bidirectional"))
      (node (ref "IC2") (pin "1") (pinfunction "GND_1") (pintype "input"))
      (node (ref "IC4") (pin "15") (pinfunction "CDVSS_15") (pintype "power_in"))
      (node (ref "IC4") (pin "19") (pinfunction "ANA18VSS_19") (pintype "power_in"))
      (node (ref "IC4") (pin "35") (pinfunction "IO_VSS2_35") (pintype "power_in"))
      (node (ref "IC4") (pin "36") (pinfunction "CORE_VSS_36") (pintype "power_in"))
      (node (ref "IC4") (pin "47") (pinfunction "IO_VSS1_47") (pintype "power_in"))
      (node (ref "IC4") (pin "6") (pinfunction "TXD_3_6") (pintype "bidirectional"))
      (node (ref "IC5") (pin "1") (pinfunction "GND_1") (pintype "input"))
      (node (ref "JP2") (pin "3") (pinfunction "3_3") (pintype "passive"))
      (node (ref "JP3") (pin "1") (pinfunction "1_1") (pintype "passive"))
      (node (ref "JP5") (pin "GND1") (pinfunction "GND_GND1") (pintype "bidirectional"))
      (node (ref "R21") (pin "1") (pinfunction "1_1") (pintype "passive"))
      (node (ref "R26") (pin "2") (pinfunction "2_2") (pintype "passive"))
      (node (ref "R27") (pin "2") (pinfunction "2_2") (pintype "passive"))
      (node (ref "R28") (pin "2") (pinfunction "2_2") (pintype "passive"))
      (node (ref "R29") (pin "2") (pinfunction "2_2") (pintype "passive"))
      (node (ref "R36") (pin "2") (pinfunction "2_2") (pintype "passive"))
      (node (ref "R6") (pin "2") (pinfunction "2_2") (pintype "passive"))
      (node (ref "RJ1") (pin "GND") (pinfunction "GND_GND") (pintype "bidirectional"))
      (node (ref "RJ1") (pin "SHIELD0") (pinfunction "SHIELD0_SHIELD0") (pintype "bidirectional"))
      (node (ref "RJ1") (pin "SHIELD1") (pinfunction "SHIELD1_SHIELD1") (pintype "bidirectional"))
      (node (ref "SV1") (pin "29") (pinfunction "29_29") (pintype "passive"))
      (node (ref "SV1") (pin "30") (pinfunction "30_30") (pintype "passive"))
      (node (ref "U$1") (pin "2") (pinfunction "GND_2") (pintype "power_in"))
      (node (ref "U$2") (pin "4") (pinfunction "VSS_4") (pintype "bidirectional"))
      (node (ref "U$3") (pin "13") (pinfunction "VSS_13") (pintype "bidirectional"))
      (node (ref "U$3") (pin "31") (pinfunction "AVSS_31") (pintype "bidirectional"))
      (node (ref "U$3") (pin "36") (pinfunction "VSS_36") (pintype "bidirectional"))
      (node (ref "U$3") (pin "45") (pinfunction "VSS_45") (pintype "bidirectional"))
      (node (ref "U$3") (pin "53") (pinfunction "VSS_53") (pintype "bidirectional"))
      (node (ref "U$3") (pin "63") (pinfunction "VSS_63") (pintype "bidirectional"))
      (node (ref "U$3") (pin "75") (pinfunction "VSS_75") (pintype "bidirectional"))
      (node (ref "U$3") (pin "84") (pinfunction "VSS_84") (pintype "bidirectional"))
      (node (ref "U$3") (pin "92") (pinfunction "VSS_92") (pintype "bidirectional"))
      (node (ref "U$7") (pin "2") (pinfunction "GND_2") (pintype "power_in"))
      (node (ref "U1") (pin "6") (pinfunction "GND_6") (pintype "bidirectional"))
      (node (ref "U1") (pin "CD2") (pinfunction "SHIELD_CD2") (pintype "bidirectional"))
      (node (ref "U1") (pin "GND1") (pinfunction "SHIELD_GND1") (pintype "bidirectional"))
      (node (ref "U1") (pin "GND2") (pinfunction "SHIELD_GND2") (pintype "bidirectional"))
      (node (ref "U2") (pin "16") (pinfunction "DGND1_16") (pintype "power_in"))
      (node (ref "U2") (pin "20") (pinfunction "DGND2_20") (pintype "power_in"))
      (node (ref "U2") (pin "21") (pinfunction "DGND3_21") (pintype "power_in"))
      (node (ref "U2") (pin "22") (pinfunction "DGND4_22") (pintype "power_in"))
      (node (ref "U2") (pin "4") (pinfunction "DGND_4") (pintype "power_in"))
      (node (ref "X1") (pin "2") (pinfunction "S_2") (pintype "passive"))
      (node (ref "X3") (pin "4") (pinfunction "4_4") (pintype "passive"))
      (node (ref "X3") (pin "M1") (pinfunction "S1_M1") (pintype "passive"))
      (node (ref "X3") (pin "M2") (pinfunction "S2_M2") (pintype "passive"))
      (node (ref "Y3") (pin "2") (pinfunction "3_2") (pintype "passive"))
      (node (ref "Y3") (pin "4") (pinfunction "3_4") (pintype "passive"))
    )
    (net (code "20") (name "LED_ACT") (class "Default")
      (node (ref "IC4") (pin "26") (pinfunction "LED_ACTCOL_26") (pintype "bidirectional"))
      (node (ref "RJ1") (pin "G-") (pinfunction "G-_G-") (pintype "bidirectional"))
    )
    (net (code "21") (name "LED_LINK") (class "Default")
      (node (ref "IC4") (pin "28") (pinfunction "LED_LNK_28") (pintype "bidirectional"))
      (node (ref "RJ1") (pin "Y-") (pinfunction "Y-_Y-") (pintype "bidirectional"))
    )
    (net (code "22") (name "MCLR") (class "Default")
      (node (ref "JP2") (pin "1") (pinfunction "1_1") (pintype "passive"))
      (node (ref "R12") (pin "1") (pinfunction "1_1") (pintype "passive"))
      (node (ref "U$3") (pin "15") (pinfunction "MCLR_15") (pintype "bidirectional"))
    )
    (net (code "23") (name "MISO") (class "Default")
      (node (ref "R16") (pin "1") (pinfunction "1_1") (pintype "passive"))
      (node (ref "U$2") (pin "2") (pinfunction "SO_2") (pintype "bidirectional"))
      (node (ref "U$3") (pin "64") (pinfunction "EBIA9/RPF4/SDA5/PMA9/RF4_64") (pintype "bidirectional"))
      (node (ref "U1") (pin "7") (pinfunction "DO_7") (pintype "bidirectional"))
    )
    (net (code "24") (name "MOSI") (class "Default")
      (node (ref "U$2") (pin "5") (pinfunction "SI_5") (pintype "bidirectional"))
      (node (ref "U$3") (pin "47") (pinfunction "AN32/AETXD0/RPD14/RD14_47") (pintype "bidirectional"))
      (node (ref "U1") (pin "3") (pinfunction "DI_3") (pintype "bidirectional"))
    )
    (net (code "25") (name "Net-(C28-Pad1)") (class "Default")
      (node (ref "C28") (pin "1") (pinfunction "1_1") (pintype "passive"))
      (node (ref "R12") (pin "2") (pinfunction "2_2") (pintype "passive"))
      (node (ref "R9") (pin "1") (pinfunction "1_1") (pintype "passive"))
    )
    (net (code "26") (name "Net-(C36-Pad2)") (class "Default")
      (node (ref "C36") (pin "2") (pinfunction "2_2") (pintype "passive"))
      (node (ref "R23") (pin "1") (pinfunction "1_1") (pintype "passive"))
    )
    (net (code "27") (name "Net-(C37-Pad2)") (class "Default")
      (node (ref "C37") (pin "2") (pinfunction "2_2") (pintype "passive"))
      (node (ref "R24") (pin "1") (pinfunction "1_1") (pintype "passive"))
    )
    (net (code "28") (name "Net-(C39-Pad2)") (class "Default")
      (node (ref "C39") (pin "2") (pinfunction "2_2") (pintype "passive"))
      (node (ref "R22") (pin "1") (pinfunction "1_1") (pintype "passive"))
    )
    (net (code "29") (name "Net-(C43-Pad1)") (class "Default")
      (node (ref "C43") (pin "1") (pinfunction "1_1") (pintype "passive"))
      (node (ref "R31") (pin "1") (pinfunction "1_1") (pintype "passive"))
    )
    (net (code "30") (name "Net-(C43-Pad2)") (class "Default")
      (node (ref "C43") (pin "2") (pinfunction "2_2") (pintype "passive"))
      (node (ref "J1") (pin "TIP") (pinfunction "TIP_TIP") (pintype "bidirectional"))
      (node (ref "R34") (pin "1") (pinfunction "1_1") (pintype "passive"))
    )
    (net (code "31") (name "Net-(C44-Pad1)") (class "Default")
      (node (ref "C44") (pin "1") (pinfunction "1_1") (pintype "passive"))
      (node (ref "R32") (pin "1") (pinfunction "1_1") (pintype "passive"))
    )
    (net (code "32") (name "Net-(C44-Pad2)") (class "Default")
      (node (ref "C44") (pin "2") (pinfunction "2_2") (pintype "passive"))
      (node (ref "J1") (pin "RING1") (pinfunction "RING1_RING1") (pintype "bidirectional"))
      (node (ref "R33") (pin "1") (pinfunction "1_1") (pintype "passive"))
    )
    (net (code "33") (name "Net-(IC1-I{slash}O_1)") (class "Default")
      (node (ref "IC1") (pin "1") (pinfunction "I/O_1_1") (pintype "bidirectional"))
      (node (ref "X3") (pin "2") (pinfunction "2_2") (pintype "passive"))
    )
    (net (code "34") (name "Net-(IC1-I{slash}O_2)") (class "Default")
      (node (ref "IC1") (pin "3") (pinfunction "I/O_2_3") (pintype "bidirectional"))
      (node (ref "X3") (pin "3") (pinfunction "3_3") (pintype "passive"))
    )
    (net (code "35") (name "Net-(IC4-IP_PH_M)") (class "Default")
      (node (ref "IC4") (pin "20") (pinfunction "IP_PH_M_20") (pintype "input"))
      (node (ref "R10") (pin "1") (pinfunction "1_1") (pintype "passive"))
    )
    (net (code "36") (name "Net-(IC4-IP_PH_P)") (class "Default")
      (node (ref "IC4") (pin "21") (pinfunction "IP_PH_P_21") (pintype "input"))
      (node (ref "R7") (pin "1") (pinfunction "1_1") (pintype "passive"))
    )
    (net (code "37") (name "Net-(IC4-RX_DV)") (class "Default")
      (node (ref "IC4") (pin "39") (pinfunction "RX_DV_39") (pintype "bidirectional"))
      (node (ref "R20") (pin "2") (pinfunction "2_2") (pintype "passive"))
    )
    (net (code "38") (name "Net-(IC4-VREF)") (class "Default")
      (node (ref "IC4") (pin "24") (pinfunction "VREF_24") (pintype "bidirectional"))
      (node (ref "R6") (pin "1") (pinfunction "1_1") (pintype "passive"))
    )
    (net (code "39") (name "Net-(JP5-VCC)") (class "Default")
      (node (ref "F1") (pin "1") (pinfunction "1_1") (pintype "passive"))
      (node (ref "JP5") (pin "VBUS1") (pinfunction "VCC_VBUS1") (pintype "bidirectional"))
      (node (ref "X1") (pin "1") (pinfunction "S_1") (pintype "passive"))
    )
    (net (code "40") (name "Net-(R42-Pad2)") (class "Default")
      (node (ref "R42") (pin "2") (pinfunction "2_2") (pintype "passive"))
      (node (ref "RJ1") (pin "G+") (pinfunction "G+_G+") (pintype "bidirectional"))
    )
    (net (code "41") (name "Net-(R43-Pad1)") (class "Default")
      (node (ref "R43") (pin "1") (pinfunction "1_1") (pintype "passive"))
      (node (ref "RJ1") (pin "Y+") (pinfunction "Y+_Y+") (pintype "bidirectional"))
    )
    (net (code "42") (name "Net-(U2A-GBUF)") (class "Default")
      (node (ref "R23") (pin "2") (pinfunction "2_2") (pintype "passive"))
      (node (ref "U2") (pin "42") (pinfunction "GBUF_42") (pintype "bidirectional"))
    )
    (net (code "43") (name "Net-(U2A-GPIO0)") (class "Default")
      (node (ref "R26") (pin "1") (pinfunction "1_1") (pintype "passive"))
      (node (ref "U2") (pin "33") (pinfunction "GPIO0_33") (pintype "bidirectional"))
    )
    (net (code "44") (name "Net-(U2A-GPIO1)") (class "Default")
      (node (ref "R27") (pin "1") (pinfunction "1_1") (pintype "passive"))
      (node (ref "U2") (pin "34") (pinfunction "GPIO1_34") (pintype "bidirectional"))
    )
    (net (code "45") (name "Net-(U2A-GPIO2{slash}DCLK)") (class "Default")
      (node (ref "R28") (pin "1") (pinfunction "1_1") (pintype "passive"))
      (node (ref "U2") (pin "9") (pinfunction "GPIO2/DCLK_9") (pintype "bidirectional"))
    )
    (net (code "46") (name "Net-(U2A-GPIO3{slash}SDATA)") (class "Default")
      (node (ref "R29") (pin "1") (pinfunction "1_1") (pintype "passive"))
      (node (ref "U2") (pin "10") (pinfunction "GPIO3/SDATA_10") (pintype "bidirectional"))
    )
    (net (code "47") (name "Net-(U2A-LEFT)") (class "Default")
      (node (ref "R22") (pin "2") (pinfunction "2_2") (pintype "passive"))
      (node (ref "R31") (pin "2") (pinfunction "2_2") (pintype "passive"))
      (node (ref "U2") (pin "46") (pinfunction "LEFT_46") (pintype "bidirectional"))
    )
    (net (code "48") (name "Net-(U2A-RCAP)") (class "Default")
      (node (ref "R25") (pin "2") (pinfunction "2_2") (pintype "passive"))
      (node (ref "U2") (pin "44") (pinfunction "RCAP_44") (pintype "bidirectional"))
    )
    (net (code "49") (name "Net-(U2A-RIGHT)") (class "Default")
      (node (ref "R24") (pin "2") (pinfunction "2_2") (pintype "passive"))
      (node (ref "R32") (pin "2") (pinfunction "2_2") (pintype "passive"))
      (node (ref "U2") (pin "39") (pinfunction "RIGHT_39") (pintype "bidirectional"))
    )
    (net (code "50") (name "Net-(U2A-RX)") (class "Default")
      (node (ref "R30") (pin "1") (pinfunction "1_1") (pintype "passive"))
      (node (ref "U2") (pin "26") (pinfunction "RX_26") (pintype "bidirectional"))
    )
    (net (code "51") (name "Net-(U2A-XTALI)") (class "Default")
      (node (ref "C50") (pin "1") (pinfunction "1_1") (pintype "passive"))
      (node (ref "R35") (pin "2") (pinfunction "2_2") (pintype "passive"))
      (node (ref "U2") (pin "18") (pinfunction "XTALI_18") (pintype "bidirectional"))
      (node (ref "Y3") (pin "1") (pinfunction "2_1") (pintype "passive"))
    )
    (net (code "52") (name "Net-(U2A-XTALO)") (class "Default")
      (node (ref "C49") (pin "1") (pinfunction "1_1") (pintype "passive"))
      (node (ref "R35") (pin "1") (pinfunction "1_1") (pintype "passive"))
      (node (ref "U2") (pin "17") (pinfunction "XTALO_17") (pintype "bidirectional"))
      (node (ref "Y3") (pin "3") (pinfunction "1_3") (pintype "passive"))
    )
    (net (code "53") (name "PGEC") (class "Default")
      (node (ref "JP2") (pin "5") (pinfunction "5_5") (pintype "passive"))
      (node (ref "U$3") (pin "24") (pinfunction "PGEC1/AN1/RPB1/RB1_24") (pintype "bidirectional"))
    )
    (net (code "54") (name "PGED") (class "Default")
      (node (ref "JP2") (pin "4") (pinfunction "4_4") (pintype "passive"))
      (node (ref "U$3") (pin "25") (pinfunction "PGED1/AN0/RPB0/RB0_25") (pintype "bidirectional"))
    )
    (net (code "55") (name "PH0") (class "Default")
      (node (ref "U$1") (pin "3") (pinfunction "OUT_3") (pintype "output"))
      (node (ref "U$3") (pin "49") (pinfunction "OSC1/CLKI/RC12_49") (pintype "bidirectional"))
    )
    (net (code "56") (name "RA2") (class "Default")
      (node (ref "SV1") (pin "4") (pinfunction "4_4") (pintype "passive"))
      (node (ref "U$3") (pin "59") (pinfunction "EBICS0/SCL2/RA2_59") (pintype "bidirectional"))
    )
    (net (code "57") (name "RA3") (class "Default")
      (node (ref "SV1") (pin "3") (pinfunction "3_3") (pintype "passive"))
      (node (ref "U$3") (pin "60") (pinfunction "EBIRDY1/SDA2/RA3_60") (pintype "bidirectional"))
    )
    (net (code "58") (name "RA4") (class "Default")
      (node (ref "SV1") (pin "6") (pinfunction "6_6") (pintype "passive"))
      (node (ref "U$3") (pin "61") (pinfunction "EBIA14/PMCS1/PMA14/RA4_61") (pintype "bidirectional"))
    )
    (net (code "59") (name "RA5") (class "Default")
      (node (ref "SV1") (pin "28") (pinfunction "28_28") (pintype "passive"))
      (node (ref "U$3") (pin "2") (pinfunction "EBIA5/AN34/PMA5/RA5_2") (pintype "bidirectional"))
    )
    (net (code "60") (name "RA6") (class "Default")
      (node (ref "SV1") (pin "15") (pinfunction "15_15") (pintype "passive"))
      (node (ref "U$3") (pin "89") (pinfunction "TRCLK/SQICLK/RA6_89") (pintype "bidirectional"))
    )
    (net (code "61") (name "RA7") (class "Default")
      (node (ref "SV1") (pin "18") (pinfunction "18_18") (pintype "passive"))
      (node (ref "U$3") (pin "90") (pinfunction "TRD3/SQID3/RA7_90") (pintype "bidirectional"))
    )
    (net (code "62") (name "RA14") (class "Default")
      (node (ref "SV1") (pin "5") (pinfunction "5_5") (pintype "passive"))
      (node (ref "U$3") (pin "66") (pinfunction "AETXCLK/RPA14/SCL1/RA14_66") (pintype "bidirectional"))
    )
    (net (code "63") (name "RD1") (class "Default")
      (node (ref "SV1") (pin "7") (pinfunction "7_7") (pintype "passive"))
      (node (ref "U$3") (pin "76") (pinfunction "RPD1/SCK1/RD1_76") (pintype "bidirectional"))
    )
    (net (code "64") (name "RD3") (class "Default")
      (node (ref "SV1") (pin "10") (pinfunction "10_10") (pintype "passive"))
      (node (ref "U$3") (pin "78") (pinfunction "EBID15/ETXCLK/RPD3/PMD15/RD3_78") (pintype "bidirectional"))
    )
    (net (code "65") (name "RD4") (class "Default")
      (node (ref "SV1") (pin "11") (pinfunction "11_11") (pintype "passive"))
      (node (ref "U$3") (pin "81") (pinfunction "SQICS0/RPD4/RD4_81") (pintype "bidirectional"))
    )
    (net (code "66") (name "RD5") (class "Default")
      (node (ref "SV1") (pin "14") (pinfunction "14_14") (pintype "passive"))
      (node (ref "U$3") (pin "82") (pinfunction "SQICS1/RPD5/RD5_82") (pintype "bidirectional"))
    )
    (net (code "67") (name "RD9") (class "Default")
      (node (ref "SV1") (pin "8") (pinfunction "8_8") (pintype "passive"))
      (node (ref "U$3") (pin "68") (pinfunction "EBIA15/RPD9/PMCS2/PMA15/RD9_68") (pintype "bidirectional"))
    )
    (net (code "68") (name "RD12") (class "Default")
      (node (ref "SV1") (pin "9") (pinfunction "9_9") (pintype "passive"))
      (node (ref "U$3") (pin "79") (pinfunction "EBID12/ETXD2/RPD12/PMD12/RD12_79") (pintype "bidirectional"))
    )
    (net (code "69") (name "RD13") (class "Default")
      (node (ref "SV1") (pin "12") (pinfunction "12_12") (pintype "passive"))
      (node (ref "U$3") (pin "80") (pinfunction "EBID13/ETXD3/PMD13/RD13_80") (pintype "bidirectional"))
    )
    (net (code "70") (name "RD_N") (class "Default")
      (node (ref "IC4") (pin "13") (pinfunction "TPRDM_13") (pintype "bidirectional"))
      (node (ref "R5") (pin "1") (pinfunction "1_1") (pintype "passive"))
      (node (ref "RJ1") (pin "RD-") (pinfunction "RD-_RD-") (pintype "bidirectional"))
    )
    (net (code "71") (name "RD_P") (class "Default")
      (node (ref "IC4") (pin "14") (pinfunction "TPRDP_14") (pintype "bidirectional"))
      (node (ref "R4") (pin "1") (pinfunction "1_1") (pintype "passive"))
      (node (ref "RJ1") (pin "RD+") (pinfunction "RD+_RD+") (pintype "bidirectional"))
    )
    (net (code "72") (name "RE0") (class "Default")
      (node (ref "SV1") (pin "17") (pinfunction "17_17") (pintype "passive"))
      (node (ref "U$3") (pin "91") (pinfunction "EBID0/PMD0/RE0_91") (pintype "bidirectional"))
    )
    (net (code "73") (name "RE1") (class "Default")
      (node (ref "SV1") (pin "20") (pinfunction "20_20") (pintype "passive"))
      (node (ref "U$3") (pin "94") (pinfunction "EBID1/PMD1/RE1_94") (pintype "bidirectional"))
    )
    (net (code "74") (name "RE2") (class "Default")
      (node (ref "SV1") (pin "24") (pinfunction "24_24") (pintype "passive"))
      (node (ref "U$3") (pin "98") (pinfunction "EBID2/PMD2/RE2_98") (pintype "bidirectional"))
    )
    (net (code "75") (name "RE3") (class "Default")
      (node (ref "SV1") (pin "23") (pinfunction "23_23") (pintype "passive"))
      (node (ref "U$3") (pin "99") (pinfunction "EBID3/RPE3/PMD3/RE3_99") (pintype "bidirectional"))
    )
    (net (code "76") (name "RE4") (class "Default")
      (node (ref "SV1") (pin "26") (pinfunction "26_26") (pintype "passive"))
      (node (ref "U$3") (pin "100") (pinfunction "EBID4/AN18/PMD4/RE4_100") (pintype "bidirectional"))
    )
    (net (code "77") (name "RE5") (class "Default")
      (node (ref "SV1") (pin "27") (pinfunction "27_27") (pintype "passive"))
      (node (ref "U$3") (pin "3") (pinfunction "EBID5/AN17/RPE5/PMD5/RE5_3") (pintype "bidirectional"))
    )
    (net (code "78") (name "REG_OUT") (class "Default")
      (node (ref "C18") (pin "1") (pinfunction "1_1") (pintype "passive"))
      (node (ref "C19") (pin "1") (pinfunction "1_1") (pintype "passive"))
      (node (ref "C24") (pin "1") (pinfunction "1_1") (pintype "passive"))
      (node (ref "C32") (pin "1") (pinfunction "1_1") (pintype "passive"))
      (node (ref "IC4") (pin "18") (pinfunction "ANA18VDD_18") (pintype "power_in"))
      (node (ref "IC4") (pin "23") (pinfunction "REG_OUT_23") (pintype "output"))
      (node (ref "IC4") (pin "37") (pinfunction "CORE_VDD_37") (pintype "power_in"))
    )
    (net (code "79") (name "RG0") (class "Default")
      (node (ref "SV1") (pin "16") (pinfunction "16_16") (pintype "passive"))
      (node (ref "U$3") (pin "88") (pinfunction "EBID8/RPG0/PMD8/RG0_88") (pintype "bidirectional"))
    )
    (net (code "80") (name "RG1") (class "Default")
      (node (ref "SV1") (pin "13") (pinfunction "13_13") (pintype "passive"))
      (node (ref "U$3") (pin "87") (pinfunction "EBID9/ETXERR/RPG1/PMD9/RG1_87") (pintype "bidirectional"))
    )
    (net (code "81") (name "RG12") (class "Default")
      (node (ref "SV1") (pin "22") (pinfunction "22_22") (pintype "passive"))
      (node (ref "U$3") (pin "96") (pinfunction "TRD1/SQID1/RG12_96") (pintype "bidirectional"))
    )
    (net (code "82") (name "RG13") (class "Default")
      (node (ref "SV1") (pin "21") (pinfunction "21_21") (pintype "passive"))
      (node (ref "U$3") (pin "97") (pinfunction "TRD0/SQID0/RG13_97") (pintype "bidirectional"))
    )
    (net (code "83") (name "RG14") (class "Default")
      (node (ref "SV1") (pin "19") (pinfunction "19_19") (pintype "passive"))
      (node (ref "U$3") (pin "95") (pinfunction "TRD2/SQID2/RG14_95") (pintype "bidirectional"))
    )
    (net (code "84") (name "RG15") (class "Default")
      (node (ref "SV1") (pin "25") (pinfunction "25_25") (pintype "passive"))
      (node (ref "U$3") (pin "1") (pinfunction "AN23/AERXERR/RG15_1") (pintype "bidirectional"))
    )
    (net (code "85") (name "SCK") (class "Default")
      (node (ref "U$2") (pin "6") (pinfunction "SCK_6") (pintype "bidirectional"))
      (node (ref "U$3") (pin "39") (pinfunction "TDI/EBIA18/AN30/RPF13/SCK5/RF13_39") (pintype "bidirectional"))
      (node (ref "U1") (pin "5") (pinfunction "SCK_5") (pintype "bidirectional"))
    )
    (net (code "86") (name "SCL") (class "Default")
      (node (ref "SV1") (pin "1") (pinfunction "1_1") (pintype "passive"))
      (node (ref "U$3") (pin "58") (pinfunction "EBIRDY2/RPF8/SCL3/RF8_58") (pintype "bidirectional"))
    )
    (net (code "87") (name "SDA") (class "Default")
      (node (ref "SV1") (pin "2") (pinfunction "2_2") (pintype "passive"))
      (node (ref "U$3") (pin "57") (pinfunction "EBIRDY3/RPF2/SDA3/RF2_57") (pintype "bidirectional"))
    )
    (net (code "88") (name "SD_CS") (class "Default")
      (node (ref "R11") (pin "1") (pinfunction "1_1") (pintype "passive"))
      (node (ref "U$3") (pin "44") (pinfunction "EBIA0/AN10/ERXD3/AETXD2/RPB15/OCFB/PMA0/RB15_44") (pintype "bidirectional"))
      (node (ref "U1") (pin "2") (pinfunction "CS_2") (pintype "bidirectional"))
    )
    (net (code "89") (name "SD_PRESENT") (class "Default")
      (node (ref "R8") (pin "1") (pinfunction "1_1") (pintype "passive"))
      (node (ref "U$3") (pin "56") (pinfunction "RPF3/USBID/RF3_56") (pintype "bidirectional"))
      (node (ref "U1") (pin "CD1") (pinfunction "SHIELD_CD1") (pintype "bidirectional"))
    )
    (net (code "90") (name "SOSCI") (class "Default")
      (node (ref "C20") (pin "2") (pinfunction "2_2") (pintype "passive"))
      (node (ref "U$3") (pin "72") (pinfunction "SOSCI/RPC13/RC13_72") (pintype "bidirectional"))
      (node (ref "X2") (pin "1") (pinfunction "1_1") (pintype "passive"))
    )
    (net (code "91") (name "SOSCO") (class "Default")
      (node (ref "C23") (pin "2") (pinfunction "2_2") (pintype "passive"))
      (node (ref "U$3") (pin "73") (pinfunction "SOSCO/RPC14/T1CK/RC14_73") (pintype "bidirectional"))
      (node (ref "X2") (pin "2") (pinfunction "2_2") (pintype "passive"))
    )
    (net (code "92") (name "TD_N") (class "Default")
      (node (ref "IC4") (pin "16") (pinfunction "TPTDM_16") (pintype "bidirectional"))
      (node (ref "R3") (pin "1") (pinfunction "1_1") (pintype "passive"))
      (node (ref "RJ1") (pin "TD-") (pinfunction "TD-_TD-") (pintype "bidirectional"))
    )
    (net (code "93") (name "TD_P") (class "Default")
      (node (ref "IC4") (pin "17") (pinfunction "TPTDP_17") (pintype "bidirectional"))
      (node (ref "R2") (pin "1") (pinfunction "1_1") (pintype "passive"))
      (node (ref "RJ1") (pin "TD+") (pinfunction "TD+_TD+") (pintype "bidirectional"))
    )
    (net (code "94") (name "U2_RX") (class "Default")
      (node (ref "JP3") (pin "3") (pinfunction "3_3") (pintype "passive"))
      (node (ref "U$3") (pin "32") (pinfunction "EBIA10/AN48/RPB8/PMA10/RB8_32") (pintype "bidirectional"))
    )
    (net (code "95") (name "U2_TX") (class "Default")
      (node (ref "JP3") (pin "2") (pinfunction "2_2") (pintype "passive"))
      (node (ref "U$3") (pin "26") (pinfunction "PGEC2/AN46/RPB6/RB6_26") (pintype "bidirectional"))
    )
    (net (code "96") (name "VBUS") (class "Default")
      (node (ref "C12") (pin "+") (pinfunction "+_+") (pintype "passive"))
      (node (ref "C13") (pin "1") (pinfunction "1_1") (pintype "passive"))
      (node (ref "C27") (pin "1") (pinfunction "1_1") (pintype "passive"))
      (node (ref "C30") (pin "+") (pinfunction "+_+") (pintype "passive"))
      (node (ref "C5") (pin "+") (pinfunction "+_+") (pintype "passive"))
      (node (ref "C52") (pin "+") (pinfunction "+_+") (pintype "passive"))
      (node (ref "C53") (pin "1") (pinfunction "1_1") (pintype "passive"))
      (node (ref "F1") (pin "2") (pinfunction "2_2") (pintype "passive"))
      (node (ref "IC1") (pin "5") (pinfunction "VBUS_5") (pintype "bidirectional"))
      (node (ref "IC2") (pin "3") (pinfunction "IN_3") (pintype "input"))
      (node (ref "IC5") (pin "3") (pinfunction "IN_3") (pintype "input"))
      (node (ref "SV1") (pin "31") (pinfunction "31_31") (pintype "passive"))
      (node (ref "SV1") (pin "32") (pinfunction "32_32") (pintype "passive"))
      (node (ref "U$3") (pin "51") (pinfunction "VBUS_51") (pintype "bidirectional"))
      (node (ref "X3") (pin "1") (pinfunction "1_1") (pintype "passive"))
    )
    (net (code "97") (name "VS_AGND") (class "Default")
      (node (ref "C33") (pin "2") (pinfunction "2_2") (pintype "passive"))
      (node (ref "C34") (pin "2") (pinfunction "2_2") (pintype "passive"))
      (node (ref "C35") (pin "2") (pinfunction "2_2") (pintype "passive"))
      (node (ref "C36") (pin "1") (pinfunction "1_1") (pintype "passive"))
      (node (ref "C37") (pin "1") (pinfunction "1_1") (pintype "passive"))
      (node (ref "C39") (pin "1") (pinfunction "1_1") (pintype "passive"))
      (node (ref "C58") (pin "2") (pinfunction "2_2") (pintype "passive"))
      (node (ref "J1") (pin "EARTH") (pinfunction "EARTH_EARTH") (pintype "bidirectional"))
      (node (ref "R21") (pin "2") (pinfunction "2_2") (pintype "passive"))
      (node (ref "R25") (pin "1") (pinfunction "1_1") (pintype "passive"))
      (node (ref "R33") (pin "2") (pinfunction "2_2") (pintype "passive"))
      (node (ref "R34") (pin "2") (pinfunction "2_2") (pintype "passive"))
      (node (ref "U2") (pin "37") (pinfunction "AGND_37") (pintype "power_in"))
      (node (ref "U2") (pin "40") (pinfunction "AGND1_40") (pintype "power_in"))
      (node (ref "U2") (pin "41") (pinfunction "AGND2_41") (pintype "power_in"))
      (node (ref "U2") (pin "47") (pinfunction "AGND3_47") (pintype "power_in"))
    )
    (net (code "98") (name "VS_AVDD") (class "Default")
      (node (ref "C33") (pin "1") (pinfunction "1_1") (pintype "passive"))
      (node (ref "C34") (pin "1") (pinfunction "1_1") (pintype "passive"))
      (node (ref "C35") (pin "1") (pinfunction "1_1") (pintype "passive"))
      (node (ref "C58") (pin "1") (pinfunction "1_1") (pintype "passive"))
      (node (ref "L1") (pin "1") (pinfunction "1_1") (pintype "passive"))
      (node (ref "U2") (pin "38") (pinfunction "AVDD_38") (pintype "power_in"))
      (node (ref "U2") (pin "43") (pinfunction "AVDD1_43") (pintype "power_in"))
      (node (ref "U2") (pin "45") (pinfunction "AVDD2_45") (pintype "power_in"))
    )
    (net (code "99") (name "VS_CVDD") (class "Default")
      (node (ref "C45") (pin "1") (pinfunction "1_1") (pintype "passive"))
      (node (ref "C46") (pin "1") (pinfunction "1_1") (pintype "passive"))
      (node (ref "C47") (pin "1") (pinfunction "1_1") (pintype "passive"))
      (node (ref "C48") (pin "1") (pinfunction "1_1") (pintype "passive"))
      (node (ref "C57") (pin "1") (pinfunction "1_1") (pintype "passive"))
      (node (ref "L2") (pin "1") (pinfunction "1_1") (pintype "passive"))
      (node (ref "U2") (pin "24") (pinfunction "CVDD2_24") (pintype "power_in"))
      (node (ref "U2") (pin "31") (pinfunction "CVDD3_31") (pintype "power_in"))
      (node (ref "U2") (pin "5") (pinfunction "CVDD_5") (pintype "power_in"))
      (node (ref "U2") (pin "7") (pinfunction "CVDD1_7") (pintype "power_in"))
    )
    (net (code "100") (name "VS_DREQ") (class "Default")
      (node (ref "U$3") (pin "6") (pinfunction "EBIA6/AN22/RPC1/PMA6/RC1_6") (pintype "bidirectional"))
      (node (ref "U2") (pin "8") (pinfunction "DREQ_8") (pintype "bidirectional"))
    )
    (net (code "101") (name "VS_MISO") (class "Default")
      (node (ref "U$3") (pin "65") (pinfunction "EBIA8/RPF5/SCL5/PMA8/RF5_65") (pintype "bidirectional"))
      (node (ref "U2") (pin "30") (pinfunction "SO_30") (pintype "bidirectional"))
    )
    (net (code "102") (name "VS_MOSI") (class "Default")
      (node (ref "U$3") (pin "67") (pinfunction "AETXEN/RPA15/SDA1/RA15_67") (pintype "bidirectional"))
      (node (ref "U2") (pin "29") (pinfunction "SI_29") (pintype "bidirectional"))
    )
    (net (code "103") (name "VS_SCK") (class "Default")
      (node (ref "U$3") (pin "69") (pinfunction "RPD10/SCK4/RD10_69") (pintype "bidirectional"))
      (node (ref "U2") (pin "28") (pinfunction "SCLK_28") (pintype "bidirectional"))
    )
    (net (code "104") (name "VS_XCS") (class "Default")
      (node (ref "U$3") (pin "5") (pinfunction "EBID7/AN15/PMD7/RE7_5") (pintype "bidirectional"))
      (node (ref "U2") (pin "23") (pinfunction "XCS_23") (pintype "bidirectional"))
    )
    (net (code "105") (name "VS_XDCS") (class "Default")
      (node (ref "U$3") (pin "4") (pinfunction "EBID6/AN16/PMD6/RE6_4") (pintype "bidirectional"))
      (node (ref "U2") (pin "13") (pinfunction "XDCS/BSYNC_13") (pintype "bidirectional"))
    )
    (net (code "106") (name "VS_XRST") (class "Default")
      (node (ref "R36") (pin "1") (pinfunction "1_1") (pintype "passive"))
      (node (ref "U$3") (pin "7") (pinfunction "EBIA12/AN21/RPC2/PMA12/RC2_7") (pintype "bidirectional"))
      (node (ref "U2") (pin "3") (pinfunction "XRESET_3") (pintype "bidirectional"))
    )
    (net (code "107") (name "_2V6") (class "Default")
      (node (ref "C51") (pin "+") (pinfunction "+_+") (pintype "passive"))
      (node (ref "C54") (pin "1") (pinfunction "1_1") (pintype "passive"))
      (node (ref "IC5") (pin "2") (pinfunction "OUT_2") (pintype "passive"))
      (node (ref "IC5") (pin "TAB") (pinfunction "OUT1_TAB") (pintype "passive"))
      (node (ref "L1") (pin "2") (pinfunction "2_2") (pintype "passive"))
      (node (ref "L2") (pin "2") (pinfunction "2_2") (pintype "passive"))
    )
    (net (code "108") (name "unconnected-(IC4-CLK2MAC-Pad25)") (class "Default")
      (node (ref "IC4") (pin "25") (pinfunction "CLK2MAC_25") (pintype "bidirectional"))
    )
    (net (code "109") (name "unconnected-(IC4-COL-Pad42)") (class "Default")
      (node (ref "IC4") (pin "42") (pinfunction "COL_42") (pintype "bidirectional"))
    )
    (net (code "110") (name "unconnected-(IC4-LED_SPD-Pad27)") (class "Default")
      (node (ref "IC4") (pin "27") (pinfunction "LED_SPD_27") (pintype "bidirectional"))
    )
    (net (code "111") (name "unconnected-(IC4-RXD_2-Pad45)") (class "Default")
      (node (ref "IC4") (pin "45") (pinfunction "RXD_2_45") (pintype "bidirectional"))
    )
    (net (code "112") (name "unconnected-(IC4-RXD_3-Pad46)") (class "Default")
      (node (ref "IC4") (pin "46") (pinfunction "RXD_3_46") (pintype "bidirectional"))
    )
    (net (code "113") (name "unconnected-(IC4-RX_CLK-Pad38)") (class "Default")
      (node (ref "IC4") (pin "38") (pinfunction "RX_CLK_38") (pintype "bidirectional"))
    )
    (net (code "114") (name "unconnected-(IC4-TCK-Pad8)") (class "Default")
      (node (ref "IC4") (pin "8") (pinfunction "TCK_8") (pintype "input"))
    )
    (net (code "115") (name "unconnected-(IC4-TDI-Pad12)") (class "Default")
      (node (ref "IC4") (pin "12") (pinfunction "TDI_12") (pintype "input"))
    )
    (net (code "116") (name "unconnected-(IC4-TDO-Pad9)") (class "Default")
      (node (ref "IC4") (pin "9") (pinfunction "TDO_9") (pintype "output"))
    )
    (net (code "117") (name "unconnected-(IC4-TMS-Pad10)") (class "Default")
      (node (ref "IC4") (pin "10") (pinfunction "TMS_10") (pintype "input"))
    )
    (net (code "118") (name "unconnected-(IC4-TRST_N-Pad11)") (class "Default")
      (node (ref "IC4") (pin "11") (pinfunction "TRST_N_11") (pintype "input"))
    )
    (net (code "119") (name "unconnected-(IC4-TXD_2-Pad5)") (class "Default")
      (node (ref "IC4") (pin "5") (pinfunction "TXD_2_5") (pintype "bidirectional"))
    )
    (net (code "120") (name "unconnected-(IC4-TX_CLK-Pad1)") (class "Default")
      (node (ref "IC4") (pin "1") (pinfunction "TX_CLK_1") (pintype "bidirectional"))
    )
    (net (code "121") (name "unconnected-(IC4-X2-Pad33)") (class "Default")
      (node (ref "IC4") (pin "33") (pinfunction "X2_33") (pintype "output"))
    )
    (net (code "122") (name "unconnected-(J1-PadRING2)") (class "Default")
      (node (ref "J1") (pin "RING2") (pinfunction "RING2_RING2") (pintype "bidirectional"))
    )
    (net (code "123") (name "unconnected-(JP2-Pad2)") (class "Default")
      (node (ref "JP2") (pin "2") (pinfunction "2_2") (pintype "passive"))
    )
    (net (code "124") (name "unconnected-(JP2-Pad6)") (class "Default")
      (node (ref "JP2") (pin "6") (pinfunction "6_6") (pintype "passive"))
    )
    (net (code "125") (name "unconnected-(JP5-D+-PadD+1)") (class "Default")
      (node (ref "JP5") (pin "D+1") (pinfunction "D+_D+1") (pintype "bidirectional"))
    )
    (net (code "126") (name "unconnected-(JP5-D--PadD-1)") (class "Default")
      (node (ref "JP5") (pin "D-1") (pinfunction "D-_D-1") (pintype "bidirectional"))
    )
    (net (code "127") (name "unconnected-(JP5-ID-PadID1)") (class "Default")
      (node (ref "JP5") (pin "ID1") (pinfunction "ID_ID1") (pintype "bidirectional"))
    )
    (net (code "128") (name "unconnected-(RJ1-PadNC)") (class "Default")
      (node (ref "RJ1") (pin "NC") (pinfunction "NC_NC") (pintype "bidirectional"))
    )
    (net (code "129") (name "unconnected-(U$1-TRI-Pad1)") (class "Default")
      (node (ref "U$1") (pin "1") (pinfunction "TRI_1") (pintype "input"))
    )
    (net (code "130") (name "unconnected-(U$3-AN2{slash}C2INB{slash}RPB2{slash}RB2-Pad23)") (class "Default")
      (node (ref "U$3") (pin "23") (pinfunction "AN2/C2INB/RPB2/RB2_23") (pintype "bidirectional"))
    )
    (net (code "131") (name "unconnected-(U$3-AN3{slash}C2INA{slash}RPB3{slash}RB3-Pad22)") (class "Default")
      (node (ref "U$3") (pin "22") (pinfunction "AN3/C2INA/RPB3/RB3_22") (pintype "bidirectional"))
    )
    (net (code "132") (name "unconnected-(U$3-AN4{slash}C1INB{slash}RB4-Pad21)") (class "Default")
      (node (ref "U$3") (pin "21") (pinfunction "AN4/C1INB/RB4_21") (pintype "bidirectional"))
    )
    (net (code "133") (name "unconnected-(U$3-AN14{slash}C1IND{slash}ECOL{slash}RPG6{slash}SCK2{slash}RG6-Pad10)") (class "Default")
      (node (ref "U$3") (pin "10") (pinfunction "AN14/C1IND/ECOL/RPG6/SCK2/RG6_10") (pintype "bidirectional"))
    )
    (net (code "134") (name "unconnected-(U$3-AN25{slash}AERXD0{slash}RPE8{slash}RE8-Pad18)") (class "Default")
      (node (ref "U$3") (pin "18") (pinfunction "AN25/AERXD0/RPE8/RE8_18") (pintype "bidirectional"))
    )
    (net (code "135") (name "unconnected-(U$3-AN26{slash}AERXD1{slash}RPE9{slash}RE9-Pad19)") (class "Default")
      (node (ref "U$3") (pin "19") (pinfunction "AN26/AERXD1/RPE9/RE9_19") (pintype "bidirectional"))
    )
    (net (code "136") (name "unconnected-(U$3-AN33{slash}AETXD1{slash}RPD15{slash}SCK6{slash}RD15-Pad48)") (class "Default")
      (node (ref "U$3") (pin "48") (pinfunction "AN33/AETXD1/RPD15/SCK6/RD15_48") (pintype "bidirectional"))
    )
    (net (code "137") (name "unconnected-(U$3-AN45{slash}C1INA{slash}RPB5{slash}RB5-Pad20)") (class "Default")
      (node (ref "U$3") (pin "20") (pinfunction "AN45/C1INA/RPB5/RB5_20") (pintype "bidirectional"))
    )
    (net (code "138") (name "unconnected-(U$3-EBIA1{slash}AN9{slash}ERXD2{slash}AETXD3{slash}RPB14{slash}SCK3{slash}PMA1{slash}RB14-Pad43)") (class "Default")
      (node (ref "U$3") (pin "43") (pinfunction "EBIA1/AN9/ERXD2/AETXD3/RPB14/SCK3/PMA1/RB14_43") (pintype "bidirectional"))
    )
    (net (code "139") (name "unconnected-(U$3-EBIA4{slash}AN13{slash}C1INC{slash}ECRS{slash}RPG7{slash}SDA4{slash}PMA4{slash}RG7-Pad11)") (class "Default")
      (node (ref "U$3") (pin "11") (pinfunction "EBIA4/AN13/C1INC/ECRS/RPG7/SDA4/PMA4/RG7_11") (pintype "bidirectional"))
    )
    (net (code "140") (name "unconnected-(U$3-EBIA7{slash}AN49{slash}RPB9{slash}PMA7{slash}RB9-Pad33)") (class "Default")
      (node (ref "U$3") (pin "33") (pinfunction "EBIA7/AN49/RPB9/PMA7/RB9_33") (pintype "bidirectional"))
    )
    (net (code "141") (name "unconnected-(U$3-EBIOE{slash}AN19{slash}RPC4{slash}PMRD{slash}RC4-Pad9)") (class "Default")
      (node (ref "U$3") (pin "9") (pinfunction "EBIOE/AN19/RPC4/PMRD/RC4_9") (pintype "bidirectional"))
    )
    (net (code "142") (name "unconnected-(U$3-EBIWE{slash}AN20{slash}RPC3{slash}PMWR{slash}RC3-Pad8)") (class "Default")
      (node (ref "U$3") (pin "8") (pinfunction "EBIWE/AN20/RPC3/PMWR/RC3_8") (pintype "bidirectional"))
    )
    (net (code "143") (name "unconnected-(U$3-OSC2{slash}CLKO{slash}RC15-Pad50)") (class "Default")
      (node (ref "U$3") (pin "50") (pinfunction "OSC2/CLKO/RC15_50") (pintype "bidirectional"))
    )
    (net (code "144") (name "unconnected-(U$3-PGED2{slash}AN47{slash}RPB7{slash}RB7-Pad27)") (class "Default")
      (node (ref "U$3") (pin "27") (pinfunction "PGED2/AN47/RPB7/RB7_27") (pintype "bidirectional"))
    )
    (net (code "145") (name "unconnected-(U$3-TDO{slash}EBIA17{slash}AN31{slash}RPF12{slash}RF12-Pad40)") (class "Default")
      (node (ref "U$3") (pin "40") (pinfunction "TDO/EBIA17/AN31/RPF12/RF12_40") (pintype "bidirectional"))
    )
    (net (code "146") (name "unconnected-(U$3-TMS{slash}EBIA16{slash}AN24{slash}RA0-Pad17)") (class "Default")
      (node (ref "U$3") (pin "17") (pinfunction "TMS/EBIA16/AN24/RA0_17") (pintype "bidirectional"))
    )
    (net (code "147") (name "unconnected-(U$3-VREF+{slash}CVREF+{slash}AN28{slash}AERXD3{slash}RA10-Pad29)") (class "Default")
      (node (ref "U$3") (pin "29") (pinfunction "VREF+/CVREF+/AN28/AERXD3/RA10_29") (pintype "bidirectional"))
    )
    (net (code "148") (name "unconnected-(U$3-VREF-{slash}CVREF-{slash}AN27{slash}AERXD2{slash}RA9-Pad28)") (class "Default")
      (node (ref "U$3") (pin "28") (pinfunction "VREF-/CVREF-/AN27/AERXD2/RA9_28") (pintype "bidirectional"))
    )
    (net (code "149") (name "unconnected-(U$7-TRI-Pad1)") (class "Default")
      (node (ref "U$7") (pin "1") (pinfunction "TRI_1") (pintype "input"))
    )
    (net (code "150") (name "unconnected-(U1-NC-Pad1)") (class "Default")
      (node (ref "U1") (pin "1") (pinfunction "NC_1") (pintype "bidirectional"))
    )
    (net (code "151") (name "unconnected-(U1-RSV-Pad8)") (class "Default")
      (node (ref "U1") (pin "8") (pinfunction "RSV_8") (pintype "bidirectional"))
    )
    (net (code "152") (name "unconnected-(U2A-LINEIN-Pad48)") (class "Default")
      (node (ref "U2") (pin "48") (pinfunction "LINEIN_48") (pintype "bidirectional"))
    )
    (net (code "153") (name "unconnected-(U2A-MICN-Pad2)") (class "Default")
      (node (ref "U2") (pin "2") (pinfunction "MICN_2") (pintype "bidirectional"))
    )
    (net (code "154") (name "unconnected-(U2A-MICP-Pad1)") (class "Default")
      (node (ref "U2") (pin "1") (pinfunction "MICP_1") (pintype "bidirectional"))
    )
    (net (code "155") (name "unconnected-(U2A-TX-Pad27)") (class "Default")
      (node (ref "U2") (pin "27") (pinfunction "TX_27") (pintype "bidirectional"))
    )
    (net (code "156") (name "unconnected-(U2A-VCO-Pad15)") (class "Default")
      (node (ref "U2") (pin "15") (pinfunction "VCO_15") (pintype "bidirectional"))
    )
  )
)
